# homeboard30.net
KiCad netlist of a schematic drawn in EAGLE
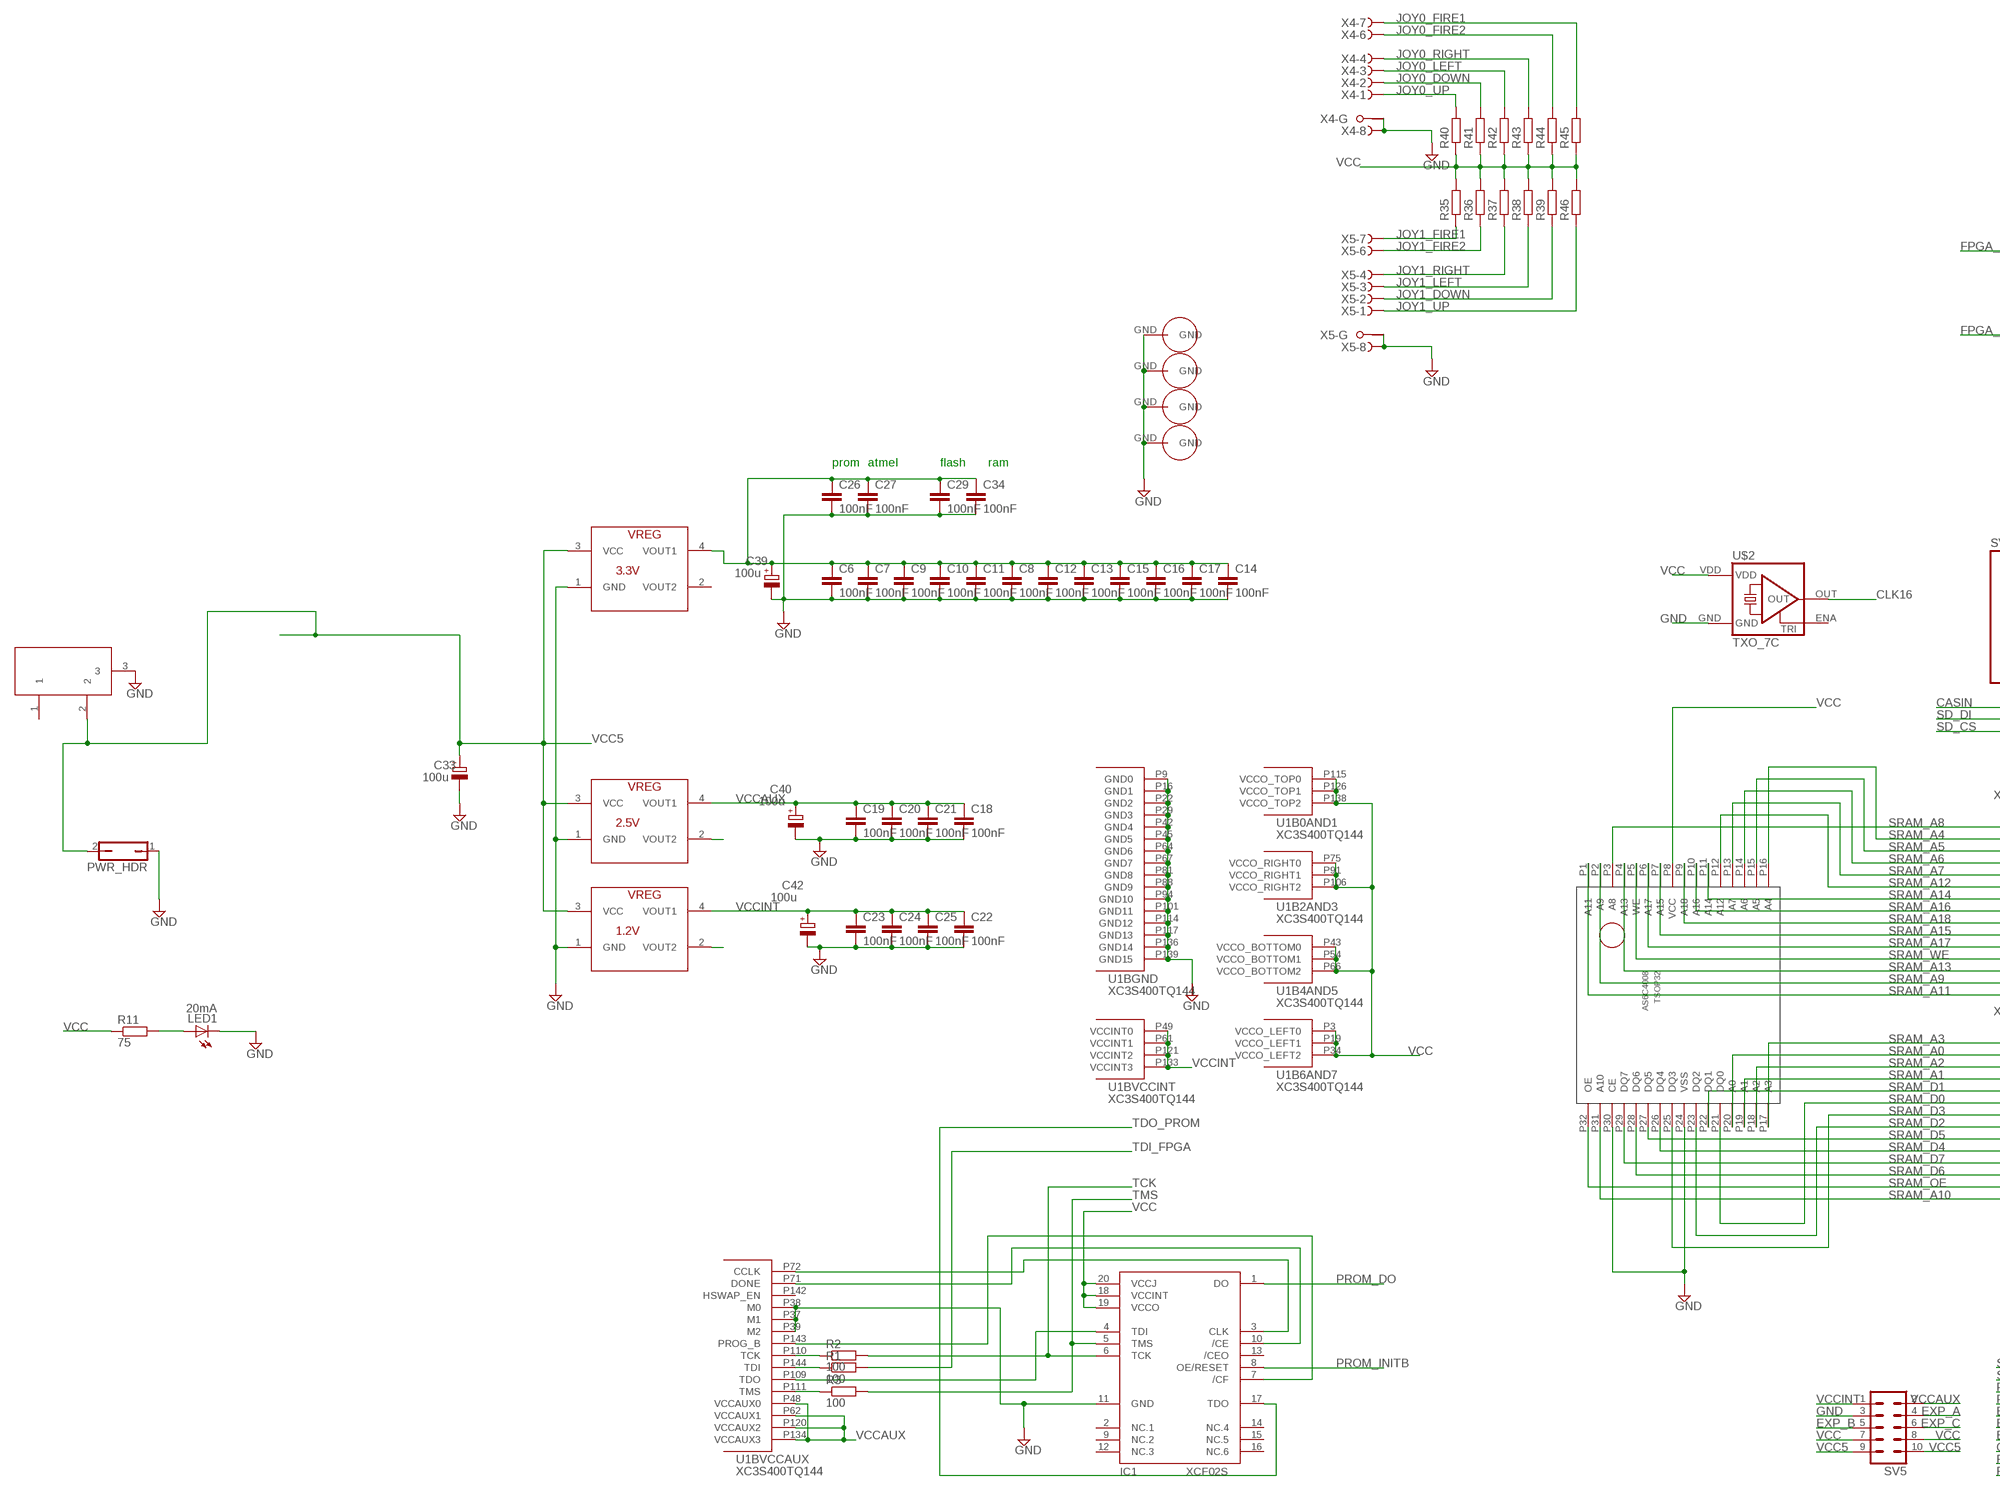
[diagram p0: schematic, sheet 1, part 1 of 3]
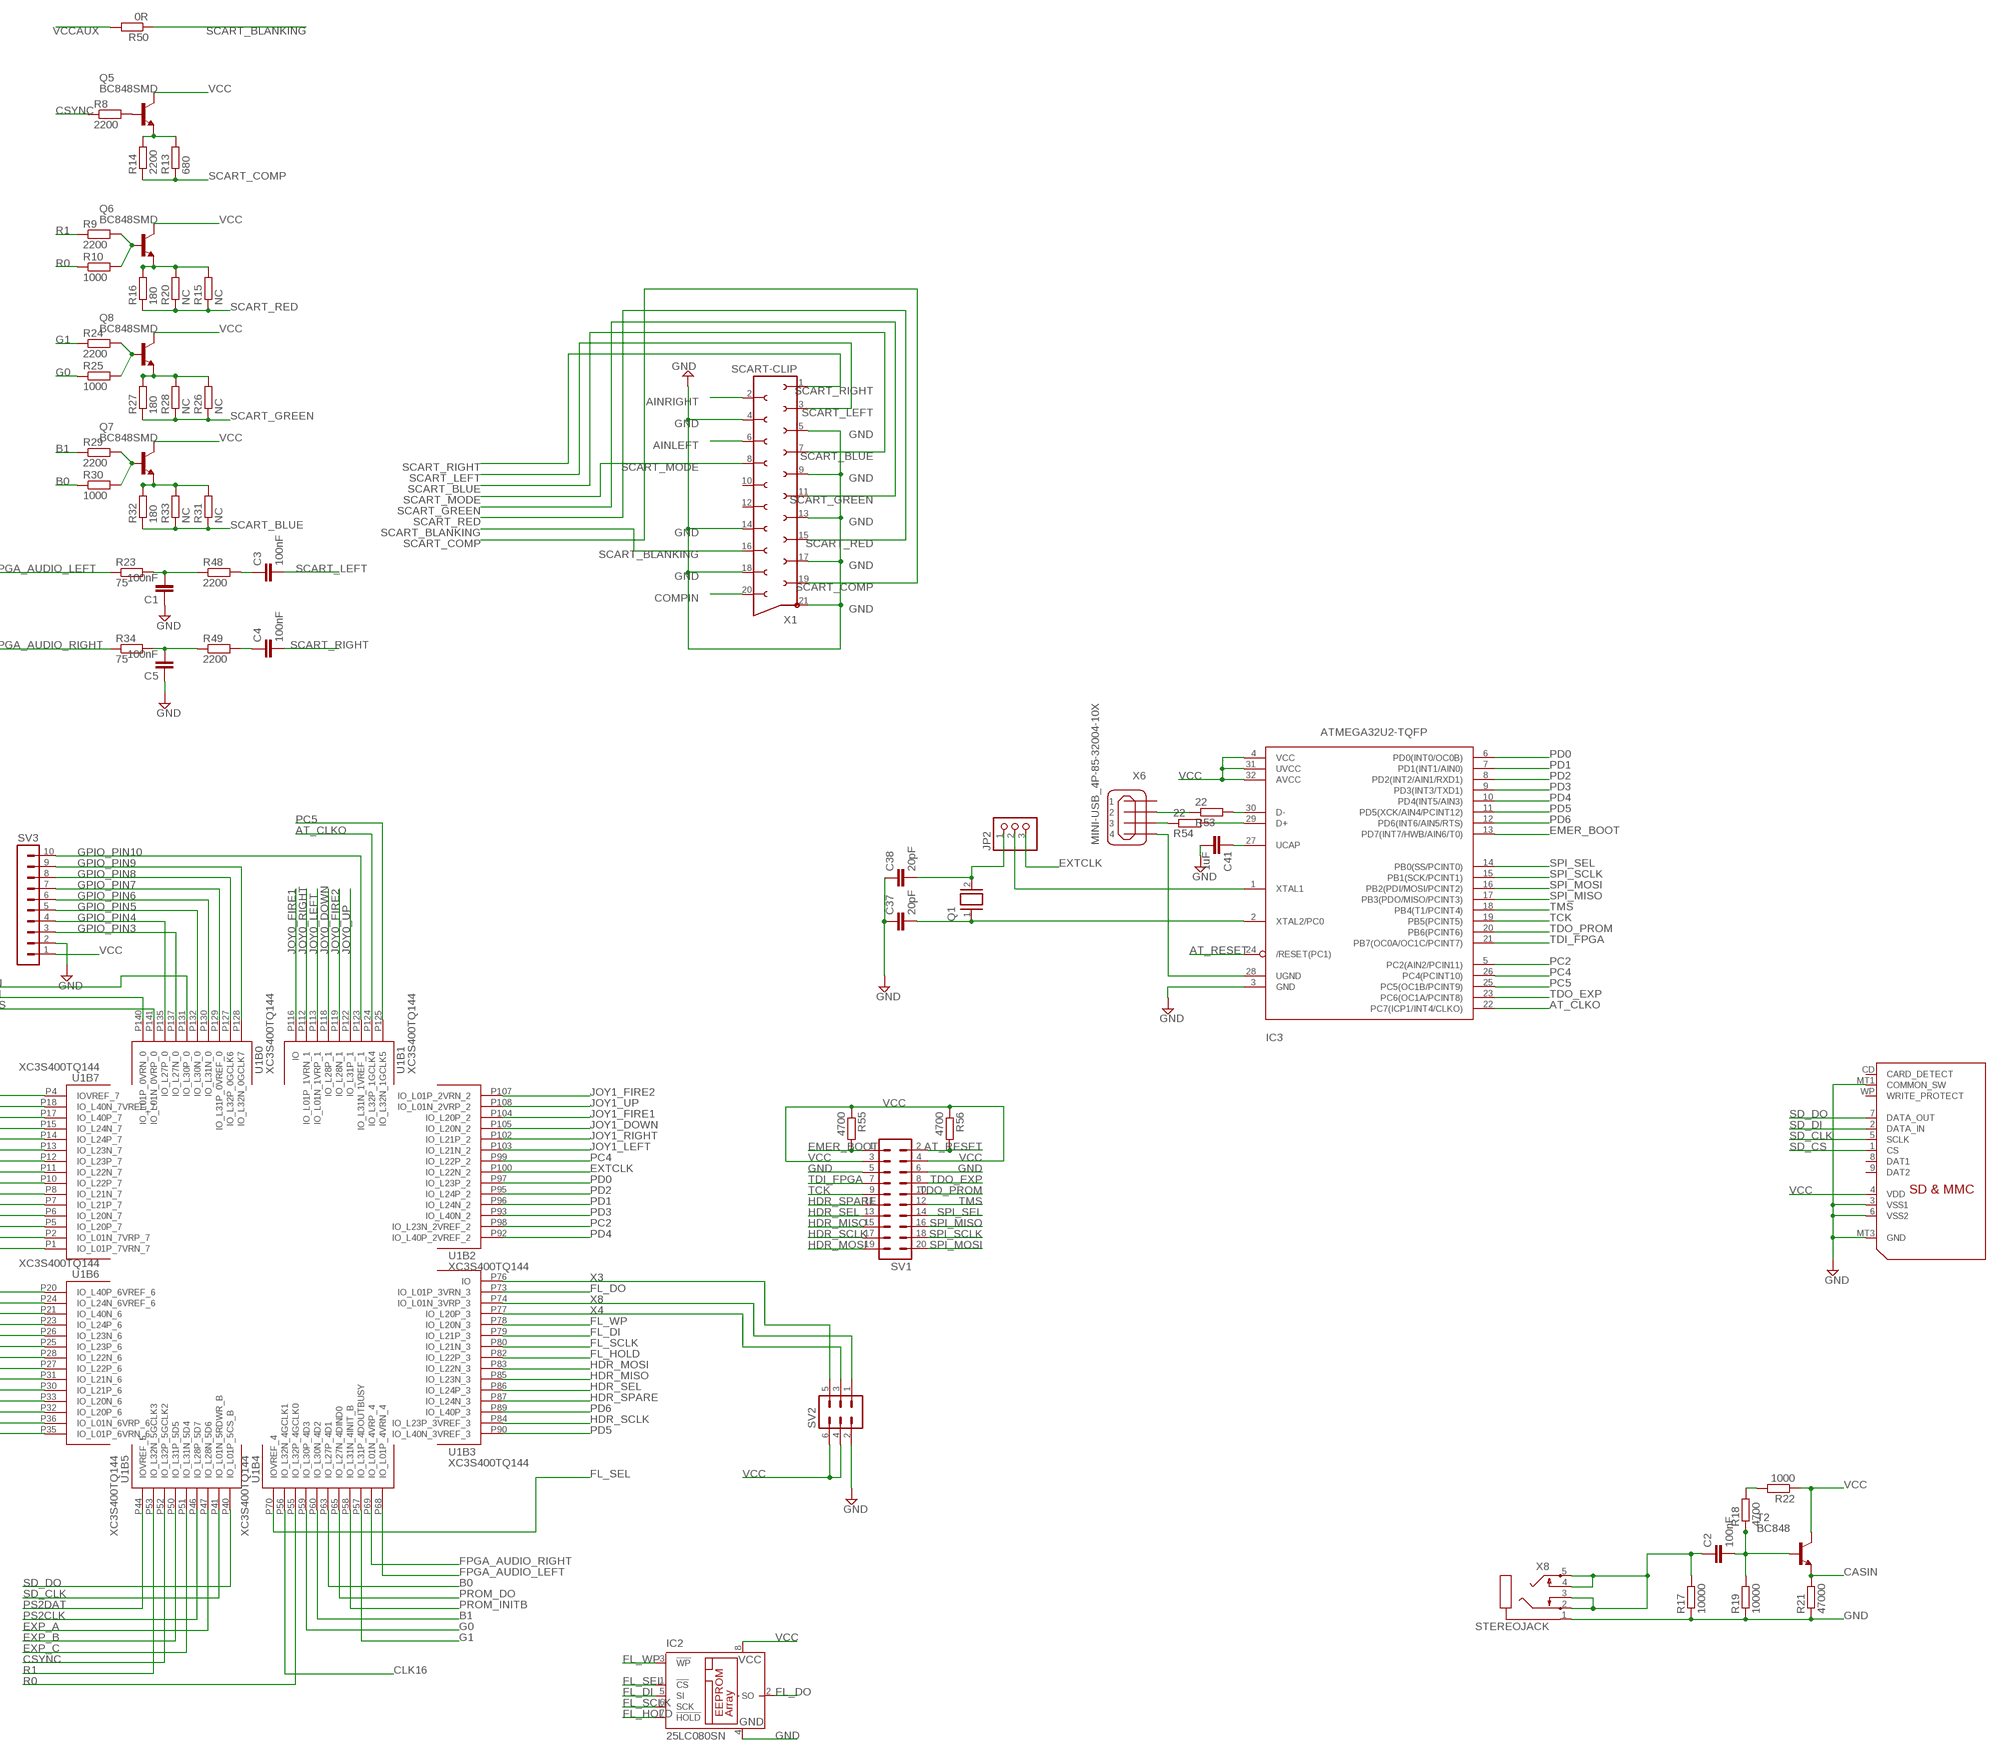
[diagram p1: schematic, sheet 1, part 2 of 3]
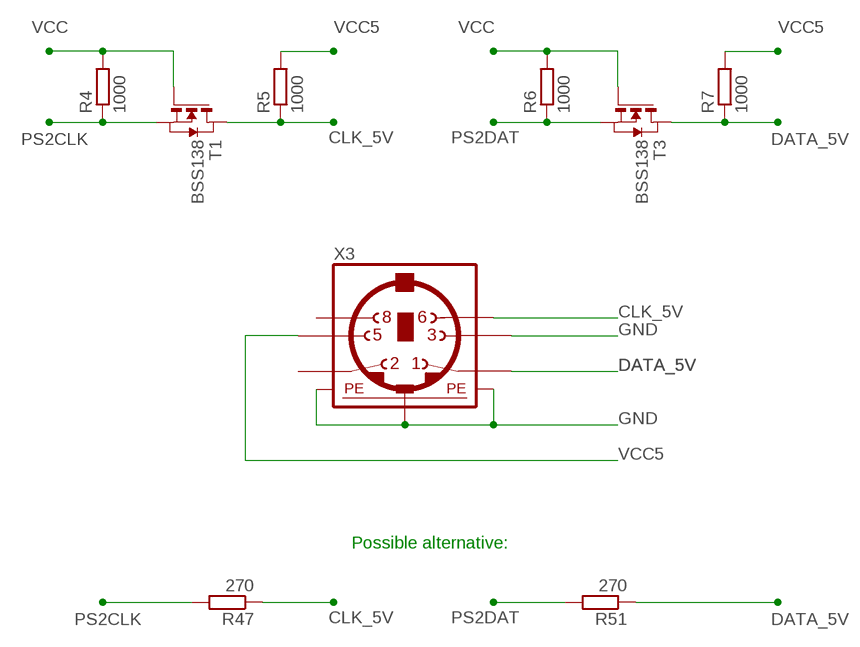
[diagram p2: schematic, sheet 1, part 3 of 3]

(export (version "E")
  (design (tool "Eeschema 10.0.6"))
  (components
    (comp (ref "C1")
      (value "100nF")
      (footprint "eagle-import:C0603")
      (libsource (lib "eagle-import") (part "resistor_C-EUC0603"))
    )
    (comp (ref "C2")
      (value "100nF")
      (footprint "eagle-import:C0603")
      (libsource (lib "eagle-import") (part "resistor_C-EUC0603"))
    )
    (comp (ref "C3")
      (value "100nF")
      (footprint "eagle-import:C0603")
      (libsource (lib "eagle-import") (part "resistor_C-EUC0603"))
    )
    (comp (ref "C4")
      (value "100nF")
      (footprint "eagle-import:C0603")
      (libsource (lib "eagle-import") (part "resistor_C-EUC0603"))
    )
    (comp (ref "C5")
      (value "100nF")
      (footprint "eagle-import:C0603")
      (libsource (lib "eagle-import") (part "resistor_C-EUC0603"))
    )
    (comp (ref "C6")
      (value "100nF")
      (footprint "eagle-import:C0603")
      (libsource (lib "eagle-import") (part "C-EUC0603"))
    )
    (comp (ref "C7")
      (value "100nF")
      (footprint "eagle-import:C0603")
      (libsource (lib "eagle-import") (part "C-EUC0603"))
    )
    (comp (ref "C8")
      (value "100nF")
      (footprint "eagle-import:C0603")
      (libsource (lib "eagle-import") (part "C-EUC0603"))
    )
    (comp (ref "C9")
      (value "100nF")
      (footprint "eagle-import:C0603")
      (libsource (lib "eagle-import") (part "C-EUC0603"))
    )
    (comp (ref "C10")
      (value "100nF")
      (footprint "eagle-import:C0603")
      (libsource (lib "eagle-import") (part "C-EUC0603"))
    )
    (comp (ref "C11")
      (value "100nF")
      (footprint "eagle-import:C0603")
      (libsource (lib "eagle-import") (part "C-EUC0603"))
    )
    (comp (ref "C12")
      (value "100nF")
      (footprint "eagle-import:C0603")
      (libsource (lib "eagle-import") (part "C-EUC0603"))
    )
    (comp (ref "C13")
      (value "100nF")
      (footprint "eagle-import:C0603")
      (libsource (lib "eagle-import") (part "C-EUC0603"))
    )
    (comp (ref "C14")
      (value "100nF")
      (footprint "eagle-import:C0603")
      (libsource (lib "eagle-import") (part "C-EUC0603"))
    )
    (comp (ref "C15")
      (value "100nF")
      (footprint "eagle-import:C0603")
      (libsource (lib "eagle-import") (part "C-EUC0603"))
    )
    (comp (ref "C16")
      (value "100nF")
      (footprint "eagle-import:C0603")
      (libsource (lib "eagle-import") (part "C-EUC0603"))
    )
    (comp (ref "C17")
      (value "100nF")
      (footprint "eagle-import:C0603")
      (libsource (lib "eagle-import") (part "C-EUC0603"))
    )
    (comp (ref "C18")
      (value "100nF")
      (footprint "eagle-import:C0603")
      (libsource (lib "eagle-import") (part "C-EUC0603"))
    )
    (comp (ref "C19")
      (value "100nF")
      (footprint "eagle-import:C0603")
      (libsource (lib "eagle-import") (part "C-EUC0603"))
    )
    (comp (ref "C20")
      (value "100nF")
      (footprint "eagle-import:C0603")
      (libsource (lib "eagle-import") (part "C-EUC0603"))
    )
    (comp (ref "C21")
      (value "100nF")
      (footprint "eagle-import:C0603")
      (libsource (lib "eagle-import") (part "C-EUC0603"))
    )
    (comp (ref "C22")
      (value "100nF")
      (footprint "eagle-import:C0603")
      (libsource (lib "eagle-import") (part "C-EUC0603"))
    )
    (comp (ref "C23")
      (value "100nF")
      (footprint "eagle-import:C0603")
      (libsource (lib "eagle-import") (part "C-EUC0603"))
    )
    (comp (ref "C24")
      (value "100nF")
      (footprint "eagle-import:C0603")
      (libsource (lib "eagle-import") (part "C-EUC0603"))
    )
    (comp (ref "C25")
      (value "100nF")
      (footprint "eagle-import:C0603")
      (libsource (lib "eagle-import") (part "C-EUC0603"))
    )
    (comp (ref "C26")
      (value "100nF")
      (footprint "eagle-import:C0603")
      (libsource (lib "eagle-import") (part "C-EUC0603"))
    )
    (comp (ref "C27")
      (value "100nF")
      (footprint "eagle-import:C0603")
      (libsource (lib "eagle-import") (part "C-EUC0603"))
    )
    (comp (ref "C29")
      (value "100nF")
      (footprint "eagle-import:C0603")
      (libsource (lib "eagle-import") (part "C-EUC0603"))
    )
    (comp (ref "C33")
      (value "100u")
      (footprint "eagle-import:PANASONIC_D")
      (libsource (lib "eagle-import") (part "CPOL-EUD"))
    )
    (comp (ref "C34")
      (value "100nF")
      (footprint "eagle-import:C0603")
      (libsource (lib "eagle-import") (part "C-EUC0603"))
    )
    (comp (ref "C37")
      (value "20pF")
      (footprint "eagle-import:C0805")
      (libsource (lib "eagle-import") (part "C-EUC0805"))
    )
    (comp (ref "C38")
      (value "20pF")
      (footprint "eagle-import:C0805")
      (libsource (lib "eagle-import") (part "C-EUC0805"))
    )
    (comp (ref "C39")
      (value "100u")
      (footprint "eagle-import:PANASONIC_D")
      (libsource (lib "eagle-import") (part "CPOL-EUD"))
    )
    (comp (ref "C40")
      (value "100u")
      (footprint "eagle-import:PANASONIC_D")
      (libsource (lib "eagle-import") (part "CPOL-EUD"))
    )
    (comp (ref "C41")
      (value "1uF")
      (footprint "eagle-import:C0805")
      (libsource (lib "eagle-import") (part "C-EUC0805"))
    )
    (comp (ref "C42")
      (value "100u")
      (footprint "eagle-import:PANASONIC_D")
      (libsource (lib "eagle-import") (part "CPOL-EUD"))
    )
    (comp (ref "IC1")
      (value "XCF02S")
      (footprint "eagle-import:VO20")
      (libsource (lib "eagle-import") (part "XCF02S"))
    )
    (comp (ref "IC2")
      (value "25LC080SN")
      (footprint "eagle-import:SO-08")
      (fields (field (name "MF") "MICROCHIP") (field (name "MPN") "25LC080/SN"))
      (libsource (lib "eagle-import") (part "25SNLC080"))
    )
    (comp (ref "IC3")
      (value "ATMEGA32U2-TQFP")
      (footprint "eagle-import:TQFP32-08")
      (libsource (lib "eagle-import") (part "ATMEGA32U2-TQFP"))
    )
    (comp (ref "JP2")
      (value "PINHD-1X3")
      (footprint "eagle-import:1X03")
      (libsource (lib "eagle-import") (part "PINHD-1X3"))
    )
    (comp (ref "LED1")
      (value "20mA")
      (footprint "eagle-import:CHIPLED_0805")
      (libsource (lib "eagle-import") (part "LEDCHIPLED_0805"))
    )
    (comp (ref "PWR_HDR")
      (value "JP1Q")
      (footprint "eagle-import:JP1")
      (libsource (lib "eagle-import") (part "JP1Q"))
    )
    (comp (ref "Q1")
      (value "XTAL/S")
      (footprint "eagle-import:QS")
      (libsource (lib "eagle-import") (part "XTAL/S"))
    )
    (comp (ref "Q5")
      (value "BC848SMD")
      (footprint "eagle-import:SOT23")
      (libsource (lib "eagle-import") (part "BC848SMD"))
    )
    (comp (ref "Q6")
      (value "BC848SMD")
      (footprint "eagle-import:SOT23")
      (libsource (lib "eagle-import") (part "BC848SMD"))
    )
    (comp (ref "Q7")
      (value "BC848SMD")
      (footprint "eagle-import:SOT23")
      (libsource (lib "eagle-import") (part "BC848SMD"))
    )
    (comp (ref "Q8")
      (value "BC848SMD")
      (footprint "eagle-import:SOT23")
      (libsource (lib "eagle-import") (part "BC848SMD"))
    )
    (comp (ref "R1")
      (value "100")
      (footprint "eagle-import:R0805")
      (libsource (lib "eagle-import") (part "R-EU_R0805"))
    )
    (comp (ref "R2")
      (value "100")
      (footprint "eagle-import:R0805")
      (libsource (lib "eagle-import") (part "R-EU_R0805"))
    )
    (comp (ref "R3")
      (value "100")
      (footprint "eagle-import:R0805")
      (libsource (lib "eagle-import") (part "R-EU_R0805"))
    )
    (comp (ref "R4")
      (value "1000")
      (footprint "eagle-import:R0805")
      (libsource (lib "eagle-import") (part "R-EU_R0805"))
    )
    (comp (ref "R5")
      (value "1000")
      (footprint "eagle-import:R0805")
      (libsource (lib "eagle-import") (part "R-EU_R0805"))
    )
    (comp (ref "R6")
      (value "1000")
      (footprint "eagle-import:R0805")
      (libsource (lib "eagle-import") (part "R-EU_R0805"))
    )
    (comp (ref "R7")
      (value "1000")
      (footprint "eagle-import:R0805")
      (libsource (lib "eagle-import") (part "R-EU_R0805"))
    )
    (comp (ref "R8")
      (value "2200")
      (footprint "eagle-import:R0805")
      (libsource (lib "eagle-import") (part "R-EU_R0805"))
    )
    (comp (ref "R9")
      (value "2200")
      (footprint "eagle-import:R0805")
      (libsource (lib "eagle-import") (part "R-EU_R0805"))
    )
    (comp (ref "R10")
      (value "1000")
      (footprint "eagle-import:R0805")
      (libsource (lib "eagle-import") (part "R-EU_R0805"))
    )
    (comp (ref "R11")
      (value "75")
      (footprint "eagle-import:M0805")
      (libsource (lib "eagle-import") (part "resistor_R-EU_M0805"))
    )
    (comp (ref "R13")
      (value "680")
      (footprint "eagle-import:R0805")
      (libsource (lib "eagle-import") (part "R-EU_R0805"))
    )
    (comp (ref "R14")
      (value "2200")
      (footprint "eagle-import:R0805")
      (libsource (lib "eagle-import") (part "R-EU_R0805"))
    )
    (comp (ref "R15")
      (value "NC")
      (footprint "eagle-import:R0805")
      (libsource (lib "eagle-import") (part "R-EU_R0805"))
    )
    (comp (ref "R16")
      (value "180")
      (footprint "eagle-import:R0805")
      (libsource (lib "eagle-import") (part "R-EU_R0805"))
    )
    (comp (ref "R17")
      (value "10000")
      (footprint "eagle-import:R0805")
      (libsource (lib "eagle-import") (part "R-EU_R0805"))
    )
    (comp (ref "R18")
      (value "4700")
      (footprint "eagle-import:R0805")
      (libsource (lib "eagle-import") (part "R-EU_R0805"))
    )
    (comp (ref "R19")
      (value "10000")
      (footprint "eagle-import:R0805")
      (libsource (lib "eagle-import") (part "R-EU_R0805"))
    )
    (comp (ref "R20")
      (value "NC")
      (footprint "eagle-import:R0805")
      (libsource (lib "eagle-import") (part "R-EU_R0805"))
    )
    (comp (ref "R21")
      (value "47000")
      (footprint "eagle-import:R0805")
      (libsource (lib "eagle-import") (part "R-EU_R0805"))
    )
    (comp (ref "R22")
      (value "1000")
      (footprint "eagle-import:R0805")
      (libsource (lib "eagle-import") (part "R-EU_R0805"))
    )
    (comp (ref "R23")
      (value "75")
      (footprint "eagle-import:M0805")
      (libsource (lib "eagle-import") (part "resistor_R-EU_M0805"))
    )
    (comp (ref "R24")
      (value "2200")
      (footprint "eagle-import:R0805")
      (libsource (lib "eagle-import") (part "R-EU_R0805"))
    )
    (comp (ref "R25")
      (value "1000")
      (footprint "eagle-import:R0805")
      (libsource (lib "eagle-import") (part "R-EU_R0805"))
    )
    (comp (ref "R26")
      (value "NC")
      (footprint "eagle-import:R0805")
      (libsource (lib "eagle-import") (part "R-EU_R0805"))
    )
    (comp (ref "R27")
      (value "180")
      (footprint "eagle-import:R0805")
      (libsource (lib "eagle-import") (part "R-EU_R0805"))
    )
    (comp (ref "R28")
      (value "NC")
      (footprint "eagle-import:R0805")
      (libsource (lib "eagle-import") (part "R-EU_R0805"))
    )
    (comp (ref "R29")
      (value "2200")
      (footprint "eagle-import:R0805")
      (libsource (lib "eagle-import") (part "R-EU_R0805"))
    )
    (comp (ref "R30")
      (value "1000")
      (footprint "eagle-import:R0805")
      (libsource (lib "eagle-import") (part "R-EU_R0805"))
    )
    (comp (ref "R31")
      (value "NC")
      (footprint "eagle-import:R0805")
      (libsource (lib "eagle-import") (part "R-EU_R0805"))
    )
    (comp (ref "R32")
      (value "180")
      (footprint "eagle-import:R0805")
      (libsource (lib "eagle-import") (part "R-EU_R0805"))
    )
    (comp (ref "R33")
      (value "NC")
      (footprint "eagle-import:R0805")
      (libsource (lib "eagle-import") (part "R-EU_R0805"))
    )
    (comp (ref "R34")
      (value "75")
      (footprint "eagle-import:M0805")
      (libsource (lib "eagle-import") (part "resistor_R-EU_M0805"))
    )
    (comp (ref "R35")
      (value "R-EU_M0805")
      (footprint "eagle-import:M0805")
      (libsource (lib "eagle-import") (part "resistor_R-EU_M0805"))
    )
    (comp (ref "R36")
      (value "R-EU_M0805")
      (footprint "eagle-import:M0805")
      (libsource (lib "eagle-import") (part "resistor_R-EU_M0805"))
    )
    (comp (ref "R37")
      (value "R-EU_M0805")
      (footprint "eagle-import:M0805")
      (libsource (lib "eagle-import") (part "resistor_R-EU_M0805"))
    )
    (comp (ref "R38")
      (value "R-EU_M0805")
      (footprint "eagle-import:M0805")
      (libsource (lib "eagle-import") (part "resistor_R-EU_M0805"))
    )
    (comp (ref "R39")
      (value "R-EU_M0805")
      (footprint "eagle-import:M0805")
      (libsource (lib "eagle-import") (part "resistor_R-EU_M0805"))
    )
    (comp (ref "R40")
      (value "R-EU_M0805")
      (footprint "eagle-import:M0805")
      (libsource (lib "eagle-import") (part "resistor_R-EU_M0805"))
    )
    (comp (ref "R41")
      (value "R-EU_M0805")
      (footprint "eagle-import:M0805")
      (libsource (lib "eagle-import") (part "resistor_R-EU_M0805"))
    )
    (comp (ref "R42")
      (value "R-EU_M0805")
      (footprint "eagle-import:M0805")
      (libsource (lib "eagle-import") (part "resistor_R-EU_M0805"))
    )
    (comp (ref "R43")
      (value "R-EU_M0805")
      (footprint "eagle-import:M0805")
      (libsource (lib "eagle-import") (part "resistor_R-EU_M0805"))
    )
    (comp (ref "R44")
      (value "R-EU_M0805")
      (footprint "eagle-import:M0805")
      (libsource (lib "eagle-import") (part "resistor_R-EU_M0805"))
    )
    (comp (ref "R45")
      (value "R-EU_M0805")
      (footprint "eagle-import:M0805")
      (libsource (lib "eagle-import") (part "resistor_R-EU_M0805"))
    )
    (comp (ref "R46")
      (value "R-EU_M0805")
      (footprint "eagle-import:M0805")
      (libsource (lib "eagle-import") (part "resistor_R-EU_M0805"))
    )
    (comp (ref "R47")
      (value "270")
      (footprint "eagle-import:R0805")
      (libsource (lib "eagle-import") (part "R-EU_R0805"))
    )
    (comp (ref "R48")
      (value "2200")
      (footprint "eagle-import:M0805")
      (libsource (lib "eagle-import") (part "resistor_R-EU_M0805"))
    )
    (comp (ref "R49")
      (value "2200")
      (footprint "eagle-import:M0805")
      (libsource (lib "eagle-import") (part "resistor_R-EU_M0805"))
    )
    (comp (ref "R50")
      (value "0R")
      (footprint "eagle-import:M0805")
      (libsource (lib "eagle-import") (part "resistor_R-EU_M0805"))
    )
    (comp (ref "R51")
      (value "270")
      (footprint "eagle-import:R0805")
      (libsource (lib "eagle-import") (part "R-EU_R0805"))
    )
    (comp (ref "R53")
      (value "22")
      (footprint "eagle-import:R0805")
      (libsource (lib "eagle-import") (part "R-EU_R0805"))
    )
    (comp (ref "R54")
      (value "22")
      (footprint "eagle-import:R0805")
      (libsource (lib "eagle-import") (part "R-EU_R0805"))
    )
    (comp (ref "R55")
      (value "4700")
      (footprint "eagle-import:R0805")
      (libsource (lib "eagle-import") (part "R-EU_R0805"))
    )
    (comp (ref "R56")
      (value "4700")
      (footprint "eagle-import:R0805")
      (libsource (lib "eagle-import") (part "R-EU_R0805"))
    )
    (comp (ref "REG1.2")
      (value "1.2V")
      (footprint "eagle-import:SOT223")
      (libsource (lib "eagle-import") (part "NX1117"))
    )
    (comp (ref "REG2.5")
      (value "2.5V")
      (footprint "eagle-import:SOT223")
      (libsource (lib "eagle-import") (part "NX1117"))
    )
    (comp (ref "REG3.3")
      (value "3.3V")
      (footprint "eagle-import:SOT223")
      (libsource (lib "eagle-import") (part "NX1117"))
    )
    (comp (ref "SV1")
      (value "MA10-2")
      (footprint "eagle-import:MA10-2")
      (fields (field (name "OC_FARNELL") "unknown") (field (name "OC_NEWARK") "unknown"))
      (libsource (lib "eagle-import") (part "MA10-2"))
    )
    (comp (ref "SV2")
      (value "MA03-2")
      (footprint "eagle-import:MA03-2")
      (libsource (lib "eagle-import") (part "MA03-2"))
    )
    (comp (ref "SV3")
      (value "MA10-1")
      (footprint "eagle-import:MA10-1")
      (libsource (lib "eagle-import") (part "MA10-1"))
    )
    (comp (ref "SV5")
      (value "MA05-2")
      (footprint "eagle-import:MA05-2")
      (libsource (lib "eagle-import") (part "MA05-2"))
    )
    (comp (ref "T1")
      (value "BSS138")
      (footprint "eagle-import:SOT-23")
      (libsource (lib "eagle-import") (part "NMOSSOT23"))
    )
    (comp (ref "T2")
      (value "BC848")
      (footprint "eagle-import:SOT23")
      (libsource (lib "eagle-import") (part "BC848"))
    )
    (comp (ref "T3")
      (value "BSS138")
      (footprint "eagle-import:SOT-23")
      (libsource (lib "eagle-import") (part "NMOSSOT23"))
    )
    (comp (ref "U$1")
      (value "GNDHOLE")
      (footprint "eagle-import:GNDHOLE")
      (libsource (lib "eagle-import") (part "GNDHOLE"))
    )
    (comp (ref "U$2")
      (value "TXO_7C")
      (footprint "eagle-import:OSC_7C")
      (libsource (lib "eagle-import") (part "TXO_7C"))
    )
    (comp (ref "U$3")
      (value "SDMMCNOHOLE")
      (footprint "eagle-import:SDCARD-NOHOLE")
      (libsource (lib "eagle-import") (part "SDMMCNOHOLE"))
    )
    (comp (ref "U$6")
      (value "AS6C4008")
      (footprint "eagle-import:TSOP32")
      (libsource (lib "eagle-import") (part "AS6C4008"))
    )
    (comp (ref "U$7")
      (value "GNDHOLE")
      (footprint "eagle-import:GNDHOLE")
      (libsource (lib "eagle-import") (part "GNDHOLE"))
    )
    (comp (ref "U$8")
      (value "GNDHOLE")
      (footprint "eagle-import:GNDHOLE")
      (libsource (lib "eagle-import") (part "GNDHOLE"))
    )
    (comp (ref "U$9")
      (value "GNDHOLE")
      (footprint "eagle-import:GNDHOLE")
      (libsource (lib "eagle-import") (part "GNDHOLE"))
    )
    (comp (ref "U1")
      (value "XC3S400TQ144")
      (footprint "eagle-import:TQ144")
      (libsource (lib "eagle-import") (part "XC3S400TQ144"))
    )
    (comp (ref "X1")
      (value "SCART-CLIP")
      (footprint "eagle-import:SCART-CLIP")
      (libsource (lib "eagle-import") (part "SCART-CLIP"))
    )
    (comp (ref "X3")
      (value "MINI_DIN_6")
      (footprint "eagle-import:M_DIN6")
      (libsource (lib "eagle-import") (part "MINI_DIN_6"))
    )
    (comp (ref "X4")
      (value "F09HPS")
      (footprint "eagle-import:F09HP")
      (libsource (lib "eagle-import") (part "F09HPS"))
    )
    (comp (ref "X5")
      (value "F09HPS")
      (footprint "eagle-import:F09HP")
      (libsource (lib "eagle-import") (part "F09HPS"))
    )
    (comp (ref "X6")
      (value "MINI-USB_4P-85-32004-10X")
      (footprint "eagle-import:85-32004-10X")
      (libsource (lib "eagle-import") (part "MINI-USB_4P-85-32004-10X"))
    )
    (comp (ref "X7")
      (value "DC21MMX")
      (footprint "eagle-import:DC-21MM")
      (libsource (lib "eagle-import") (part "DC21MMX"))
    )
    (comp (ref "X8")
      (value "STEREOJACK")
      (footprint "eagle-import:20-0137")
      (libsource (lib "eagle-import") (part "STEREOJACK"))
    )
  )
  (nets
    (net (code "1") (name "/1") (class "Default")
      (node (ref "X7") (pin "1") (pinfunction "1_1") (pintype "power_in"))
    )
    (net (code "2") (name "/AINLEFT") (class "Default")
      (node (ref "X1") (pin "6") (pinfunction "6_6") (pintype "passive"))
    )
    (net (code "3") (name "/AINRIGHT") (class "Default")
      (node (ref "X1") (pin "2") (pinfunction "2_2") (pintype "passive"))
    )
    (net (code "4") (name "/AT_CLKO") (class "Default")
      (node (ref "IC3") (pin "22") (pinfunction "PC7(ICP1/INT4/CLKO)_22") (pintype "bidirectional"))
      (node (ref "U1") (pin "P124") (pinfunction "IO_L32P_1GCLK4_P124") (pintype "bidirectional"))
    )
    (net (code "5") (name "/AT_RESET") (class "Default")
      (node (ref "IC3") (pin "24") (pinfunction "/RESET(PC1)_24") (pintype "bidirectional"))
      (node (ref "R56") (pin "2") (pinfunction "2_2") (pintype "passive"))
      (node (ref "SV1") (pin "2") (pinfunction "2_2") (pintype "passive"))
    )
    (net (code "6") (name "/B0") (class "Default")
      (node (ref "R30") (pin "1") (pinfunction "1_1") (pintype "passive"))
      (node (ref "U1") (pin "P63") (pinfunction "IO_L27P_4D1_P63") (pintype "bidirectional"))
    )
    (net (code "7") (name "/B1") (class "Default")
      (node (ref "R29") (pin "1") (pinfunction "1_1") (pintype "passive"))
      (node (ref "U1") (pin "P60") (pinfunction "IO_L30N_4D2_P60") (pintype "bidirectional"))
    )
    (net (code "8") (name "/CASIN") (class "Default")
      (node (ref "R21") (pin "2") (pinfunction "2_2") (pintype "passive"))
      (node (ref "T2") (pin "2") (pinfunction "E_2") (pintype "passive"))
      (node (ref "U1") (pin "P131") (pinfunction "IO_L30P_0_P131") (pintype "bidirectional"))
    )
    (net (code "9") (name "/CLK16") (class "Default")
      (node (ref "U$2") (pin "OUT") (pinfunction "OUT_OUT") (pintype "output"))
      (node (ref "U1") (pin "P56") (pinfunction "IO_L32N_4GCLK1_P56") (pintype "bidirectional"))
    )
    (net (code "10") (name "/CLK_5V") (class "Default")
      (node (ref "R47") (pin "1") (pinfunction "1_1") (pintype "passive"))
      (node (ref "R5") (pin "1") (pinfunction "1_1") (pintype "passive"))
      (node (ref "T1") (pin "1") (pinfunction "D_1") (pintype "passive"))
      (node (ref "X3") (pin "6") (pinfunction "6_6") (pintype "passive"))
    )
    (net (code "11") (name "/COMPIN") (class "Default")
      (node (ref "X1") (pin "20") (pinfunction "20_20") (pintype "passive"))
    )
    (net (code "12") (name "/CSYNC") (class "Default")
      (node (ref "R8") (pin "1") (pinfunction "1_1") (pintype "passive"))
      (node (ref "U1") (pin "P52") (pinfunction "IO_L32P_5GCLK2_P52") (pintype "bidirectional"))
    )
    (net (code "13") (name "/DATA_5V") (class "Default")
      (node (ref "R51") (pin "1") (pinfunction "1_1") (pintype "passive"))
      (node (ref "R7") (pin "1") (pinfunction "1_1") (pintype "passive"))
      (node (ref "T3") (pin "1") (pinfunction "D_1") (pintype "passive"))
      (node (ref "X3") (pin "1") (pinfunction "1_1") (pintype "passive"))
    )
    (net (code "14") (name "/EMER_BOOT") (class "Default")
      (node (ref "IC3") (pin "13") (pinfunction "PD7(INT7/HWB/AIN6/T0)_13") (pintype "bidirectional"))
      (node (ref "R55") (pin "2") (pinfunction "2_2") (pintype "passive"))
      (node (ref "SV1") (pin "1") (pinfunction "1_1") (pintype "passive"))
    )
    (net (code "15") (name "/EXP_A") (class "Default")
      (node (ref "SV5") (pin "4") (pinfunction "4_4") (pintype "passive"))
      (node (ref "U1") (pin "P47") (pinfunction "IO_L28N_5D6_P47") (pintype "bidirectional"))
    )
    (net (code "16") (name "/EXP_B") (class "Default")
      (node (ref "SV5") (pin "5") (pinfunction "5_5") (pintype "passive"))
      (node (ref "U1") (pin "P50") (pinfunction "IO_L31P_5D5_P50") (pintype "bidirectional"))
    )
    (net (code "17") (name "/EXP_C") (class "Default")
      (node (ref "SV5") (pin "6") (pinfunction "6_6") (pintype "passive"))
      (node (ref "U1") (pin "P51") (pinfunction "IO_L31N_5D4_P51") (pintype "bidirectional"))
    )
    (net (code "18") (name "/EXTCLK") (class "Default")
      (node (ref "JP2") (pin "3") (pinfunction "3_3") (pintype "passive"))
      (node (ref "U1") (pin "P100") (pinfunction "IO_L22N_2_P100") (pintype "bidirectional"))
    )
    (net (code "19") (name "/FL_DI") (class "Default")
      (node (ref "IC2") (pin "5") (pinfunction "SI_5") (pintype "input"))
      (node (ref "U1") (pin "P79") (pinfunction "IO_L21P_3_P79") (pintype "bidirectional"))
    )
    (net (code "20") (name "/FL_DO") (class "Default")
      (node (ref "IC2") (pin "2") (pinfunction "SO_2") (pintype "bidirectional"))
      (node (ref "U1") (pin "P73") (pinfunction "IO_L01P_3VRN_3_P73") (pintype "bidirectional"))
    )
    (net (code "21") (name "/FL_HOLD") (class "Default")
      (node (ref "IC2") (pin "7") (pinfunction "~{HOLD}_7") (pintype "input"))
      (node (ref "U1") (pin "P82") (pinfunction "IO_L22P_3_P82") (pintype "bidirectional"))
    )
    (net (code "22") (name "/FL_SCLK") (class "Default")
      (node (ref "IC2") (pin "6") (pinfunction "SCK_6") (pintype "input"))
      (node (ref "U1") (pin "P80") (pinfunction "IO_L21N_3_P80") (pintype "bidirectional"))
    )
    (net (code "23") (name "/FL_SEL") (class "Default")
      (node (ref "IC2") (pin "1") (pinfunction "~{CS}_1") (pintype "input"))
      (node (ref "U1") (pin "P70") (pinfunction "IOVREF_4_P70") (pintype "bidirectional"))
    )
    (net (code "24") (name "/FL_WP") (class "Default")
      (node (ref "IC2") (pin "3") (pinfunction "~{WP}_3") (pintype "input"))
      (node (ref "U1") (pin "P78") (pinfunction "IO_L20N_3_P78") (pintype "bidirectional"))
    )
    (net (code "25") (name "/FPGA_AUDIO_LEFT") (class "Default")
      (node (ref "R23") (pin "1") (pinfunction "1_1") (pintype "passive"))
      (node (ref "U1") (pin "P68") (pinfunction "IO_L01P_4VRN_4_P68") (pintype "bidirectional"))
    )
    (net (code "26") (name "/FPGA_AUDIO_RIGHT") (class "Default")
      (node (ref "R34") (pin "1") (pinfunction "1_1") (pintype "passive"))
      (node (ref "U1") (pin "P69") (pinfunction "IO_L01N_4VRP_4_P69") (pintype "bidirectional"))
    )
    (net (code "27") (name "/G0") (class "Default")
      (node (ref "R25") (pin "1") (pinfunction "1_1") (pintype "passive"))
      (node (ref "U1") (pin "P59") (pinfunction "IO_L30P_4D3_P59") (pintype "bidirectional"))
    )
    (net (code "28") (name "/G1") (class "Default")
      (node (ref "R24") (pin "1") (pinfunction "1_1") (pintype "passive"))
      (node (ref "U1") (pin "P57") (pinfunction "IO_L31P_4DOUTBUSY_P57") (pintype "bidirectional"))
    )
    (net (code "29") (name "/GPIO_PIN3") (class "Default")
      (node (ref "SV3") (pin "3") (pinfunction "3_3") (pintype "passive"))
      (node (ref "U1") (pin "P137") (pinfunction "IO_L27N_0_P137") (pintype "bidirectional"))
    )
    (net (code "30") (name "/GPIO_PIN4") (class "Default")
      (node (ref "SV3") (pin "4") (pinfunction "4_4") (pintype "passive"))
      (node (ref "U1") (pin "P135") (pinfunction "IO_L27P_0_P135") (pintype "bidirectional"))
    )
    (net (code "31") (name "/GPIO_PIN5") (class "Default")
      (node (ref "SV3") (pin "5") (pinfunction "5_5") (pintype "passive"))
      (node (ref "U1") (pin "P132") (pinfunction "IO_L30N_0_P132") (pintype "bidirectional"))
    )
    (net (code "32") (name "/GPIO_PIN6") (class "Default")
      (node (ref "SV3") (pin "6") (pinfunction "6_6") (pintype "passive"))
      (node (ref "U1") (pin "P130") (pinfunction "IO_L31N_0_P130") (pintype "bidirectional"))
    )
    (net (code "33") (name "/GPIO_PIN7") (class "Default")
      (node (ref "SV3") (pin "7") (pinfunction "7_7") (pintype "passive"))
      (node (ref "U1") (pin "P129") (pinfunction "IO_L31P_0VREF_0_P129") (pintype "bidirectional"))
    )
    (net (code "34") (name "/GPIO_PIN8") (class "Default")
      (node (ref "SV3") (pin "8") (pinfunction "8_8") (pintype "passive"))
      (node (ref "U1") (pin "P127") (pinfunction "IO_L32P_0GCLK6_P127") (pintype "bidirectional"))
    )
    (net (code "35") (name "/GPIO_PIN9") (class "Default")
      (node (ref "SV3") (pin "9") (pinfunction "9_9") (pintype "passive"))
      (node (ref "U1") (pin "P128") (pinfunction "IO_L32N_0GCLK7_P128") (pintype "bidirectional"))
    )
    (net (code "36") (name "/GPIO_PIN10") (class "Default")
      (node (ref "SV3") (pin "10") (pinfunction "10_10") (pintype "passive"))
      (node (ref "U1") (pin "P123") (pinfunction "IO_L31N_1VREF_1_P123") (pintype "bidirectional"))
    )
    (net (code "37") (name "/HDR_MISO") (class "Default")
      (node (ref "SV1") (pin "15") (pinfunction "15_15") (pintype "passive"))
      (node (ref "U1") (pin "P85") (pinfunction "IO_L23N_3_P85") (pintype "bidirectional"))
    )
    (net (code "38") (name "/HDR_MOSI") (class "Default")
      (node (ref "SV1") (pin "19") (pinfunction "19_19") (pintype "passive"))
      (node (ref "U1") (pin "P83") (pinfunction "IO_L22N_3_P83") (pintype "bidirectional"))
    )
    (net (code "39") (name "/HDR_SCLK") (class "Default")
      (node (ref "SV1") (pin "17") (pinfunction "17_17") (pintype "passive"))
      (node (ref "U1") (pin "P84") (pinfunction "IO_L23P_3VREF_3_P84") (pintype "bidirectional"))
    )
    (net (code "40") (name "/HDR_SEL") (class "Default")
      (node (ref "SV1") (pin "13") (pinfunction "13_13") (pintype "passive"))
      (node (ref "U1") (pin "P86") (pinfunction "IO_L24P_3_P86") (pintype "bidirectional"))
    )
    (net (code "41") (name "/HDR_SPARE") (class "Default")
      (node (ref "SV1") (pin "11") (pinfunction "11_11") (pintype "passive"))
      (node (ref "U1") (pin "P87") (pinfunction "IO_L24N_3_P87") (pintype "bidirectional"))
    )
    (net (code "42") (name "/JOY0_DOWN") (class "Default")
      (node (ref "R41") (pin "2") (pinfunction "2_2") (pintype "passive"))
      (node (ref "U1") (pin "P118") (pinfunction "IO_L28P_1_P118") (pintype "bidirectional"))
      (node (ref "X4") (pin "2") (pinfunction "F_2") (pintype "passive"))
    )
    (net (code "43") (name "/JOY0_FIRE1") (class "Default")
      (node (ref "R45") (pin "2") (pinfunction "2_2") (pintype "passive"))
      (node (ref "U1") (pin "P116") (pinfunction "IO_P116") (pintype "bidirectional"))
      (node (ref "X4") (pin "7") (pinfunction "F_7") (pintype "passive"))
    )
    (net (code "44") (name "/JOY0_FIRE2") (class "Default")
      (node (ref "R44") (pin "2") (pinfunction "2_2") (pintype "passive"))
      (node (ref "U1") (pin "P119") (pinfunction "IO_L28N_1_P119") (pintype "bidirectional"))
      (node (ref "X4") (pin "6") (pinfunction "F_6") (pintype "passive"))
    )
    (net (code "45") (name "/JOY0_LEFT") (class "Default")
      (node (ref "R42") (pin "2") (pinfunction "2_2") (pintype "passive"))
      (node (ref "U1") (pin "P113") (pinfunction "IO_L01N_1VRP_1_P113") (pintype "bidirectional"))
      (node (ref "X4") (pin "3") (pinfunction "F_3") (pintype "passive"))
    )
    (net (code "46") (name "/JOY0_RIGHT") (class "Default")
      (node (ref "R43") (pin "2") (pinfunction "2_2") (pintype "passive"))
      (node (ref "U1") (pin "P112") (pinfunction "IO_L01P_1VRN_1_P112") (pintype "bidirectional"))
      (node (ref "X4") (pin "4") (pinfunction "F_4") (pintype "passive"))
    )
    (net (code "47") (name "/JOY0_UP") (class "Default")
      (node (ref "R40") (pin "2") (pinfunction "2_2") (pintype "passive"))
      (node (ref "U1") (pin "P122") (pinfunction "IO_L31P_1_P122") (pintype "bidirectional"))
      (node (ref "X4") (pin "1") (pinfunction "F_1") (pintype "passive"))
    )
    (net (code "48") (name "/JOY1_DOWN") (class "Default")
      (node (ref "R39") (pin "1") (pinfunction "1_1") (pintype "passive"))
      (node (ref "U1") (pin "P105") (pinfunction "IO_L20N_2_P105") (pintype "bidirectional"))
      (node (ref "X5") (pin "2") (pinfunction "F_2") (pintype "passive"))
    )
    (net (code "49") (name "/JOY1_FIRE1") (class "Default")
      (node (ref "R35") (pin "1") (pinfunction "1_1") (pintype "passive"))
      (node (ref "U1") (pin "P104") (pinfunction "IO_L20P_2_P104") (pintype "bidirectional"))
      (node (ref "X5") (pin "7") (pinfunction "F_7") (pintype "passive"))
    )
    (net (code "50") (name "/JOY1_FIRE2") (class "Default")
      (node (ref "R36") (pin "1") (pinfunction "1_1") (pintype "passive"))
      (node (ref "U1") (pin "P107") (pinfunction "IO_L01P_2VRN_2_P107") (pintype "bidirectional"))
      (node (ref "X5") (pin "6") (pinfunction "F_6") (pintype "passive"))
    )
    (net (code "51") (name "/JOY1_LEFT") (class "Default")
      (node (ref "R38") (pin "1") (pinfunction "1_1") (pintype "passive"))
      (node (ref "U1") (pin "P103") (pinfunction "IO_L21N_2_P103") (pintype "bidirectional"))
      (node (ref "X5") (pin "3") (pinfunction "F_3") (pintype "passive"))
    )
    (net (code "52") (name "/JOY1_RIGHT") (class "Default")
      (node (ref "R37") (pin "1") (pinfunction "1_1") (pintype "passive"))
      (node (ref "U1") (pin "P102") (pinfunction "IO_L21P_2_P102") (pintype "bidirectional"))
      (node (ref "X5") (pin "4") (pinfunction "F_4") (pintype "passive"))
    )
    (net (code "53") (name "/JOY1_UP") (class "Default")
      (node (ref "R46") (pin "1") (pinfunction "1_1") (pintype "passive"))
      (node (ref "U1") (pin "P108") (pinfunction "IO_L01N_2VRP_2_P108") (pintype "bidirectional"))
      (node (ref "X5") (pin "1") (pinfunction "F_1") (pintype "passive"))
    )
    (net (code "54") (name "/PC2") (class "Default")
      (node (ref "IC3") (pin "5") (pinfunction "PC2(AIN2/PCIN11)_5") (pintype "bidirectional"))
      (node (ref "U1") (pin "P98") (pinfunction "IO_L23N_2VREF_2_P98") (pintype "bidirectional"))
    )
    (net (code "55") (name "/PC4") (class "Default")
      (node (ref "IC3") (pin "26") (pinfunction "PC4(PCINT10)_26") (pintype "bidirectional"))
      (node (ref "U1") (pin "P99") (pinfunction "IO_L22P_2_P99") (pintype "bidirectional"))
    )
    (net (code "56") (name "/PC5") (class "Default")
      (node (ref "IC3") (pin "25") (pinfunction "PC5(OC1B/PCINT9)_25") (pintype "bidirectional"))
      (node (ref "U1") (pin "P125") (pinfunction "IO_L32N_1GCLK5_P125") (pintype "bidirectional"))
    )
    (net (code "57") (name "/PD0") (class "Default")
      (node (ref "IC3") (pin "6") (pinfunction "PD0(INT0/OC0B)_6") (pintype "bidirectional"))
      (node (ref "U1") (pin "P97") (pinfunction "IO_L23P_2_P97") (pintype "bidirectional"))
    )
    (net (code "58") (name "/PD1") (class "Default")
      (node (ref "IC3") (pin "7") (pinfunction "PD1(INT1/AIN0)_7") (pintype "bidirectional"))
      (node (ref "U1") (pin "P96") (pinfunction "IO_L24N_2_P96") (pintype "bidirectional"))
    )
    (net (code "59") (name "/PD2") (class "Default")
      (node (ref "IC3") (pin "8") (pinfunction "PD2(INT2/AIN1/RXD1)_8") (pintype "bidirectional"))
      (node (ref "U1") (pin "P95") (pinfunction "IO_L24P_2_P95") (pintype "bidirectional"))
    )
    (net (code "60") (name "/PD3") (class "Default")
      (node (ref "IC3") (pin "9") (pinfunction "PD3(INT3/TXD1)_9") (pintype "bidirectional"))
      (node (ref "U1") (pin "P93") (pinfunction "IO_L40N_2_P93") (pintype "bidirectional"))
    )
    (net (code "61") (name "/PD4") (class "Default")
      (node (ref "IC3") (pin "10") (pinfunction "PD4(INT5/AIN3)_10") (pintype "bidirectional"))
      (node (ref "U1") (pin "P92") (pinfunction "IO_L40P_2VREF_2_P92") (pintype "bidirectional"))
    )
    (net (code "62") (name "/PD5") (class "Default")
      (node (ref "IC3") (pin "11") (pinfunction "PD5(XCK/AIN4/PCINT12)_11") (pintype "bidirectional"))
      (node (ref "U1") (pin "P90") (pinfunction "IO_L40N_3VREF_3_P90") (pintype "bidirectional"))
    )
    (net (code "63") (name "/PD6") (class "Default")
      (node (ref "IC3") (pin "12") (pinfunction "PD6(INT6/AIN5/RTS)_12") (pintype "bidirectional"))
      (node (ref "U1") (pin "P89") (pinfunction "IO_L40P_3_P89") (pintype "bidirectional"))
    )
    (net (code "64") (name "/PROM_DO") (class "Default")
      (node (ref "IC1") (pin "1") (pinfunction "DO_1") (pintype "bidirectional"))
      (node (ref "U1") (pin "P65") (pinfunction "IO_L27N_4DIND0_P65") (pintype "bidirectional"))
    )
    (net (code "65") (name "/PROM_INITB") (class "Default")
      (node (ref "IC1") (pin "8") (pinfunction "OE/RESET_8") (pintype "bidirectional"))
      (node (ref "U1") (pin "P58") (pinfunction "IO_L31N_4INIT_B_P58") (pintype "bidirectional"))
    )
    (net (code "66") (name "/PS2CLK") (class "Default")
      (node (ref "R4") (pin "1") (pinfunction "1_1") (pintype "passive"))
      (node (ref "R47") (pin "2") (pinfunction "2_2") (pintype "passive"))
      (node (ref "T1") (pin "2") (pinfunction "S_2") (pintype "passive"))
      (node (ref "U1") (pin "P46") (pinfunction "IO_L28P_5D7_P46") (pintype "bidirectional"))
    )
    (net (code "67") (name "/PS2DAT") (class "Default")
      (node (ref "R51") (pin "2") (pinfunction "2_2") (pintype "passive"))
      (node (ref "R6") (pin "1") (pinfunction "1_1") (pintype "passive"))
      (node (ref "T3") (pin "2") (pinfunction "S_2") (pintype "passive"))
      (node (ref "U1") (pin "P44") (pinfunction "IOVREF_5_P44") (pintype "bidirectional"))
    )
    (net (code "68") (name "/R0") (class "Default")
      (node (ref "R10") (pin "1") (pinfunction "1_1") (pintype "passive"))
      (node (ref "U1") (pin "P55") (pinfunction "IO_L32P_4GCLK0_P55") (pintype "bidirectional"))
    )
    (net (code "69") (name "/R1") (class "Default")
      (node (ref "R9") (pin "1") (pinfunction "1_1") (pintype "passive"))
      (node (ref "U1") (pin "P53") (pinfunction "IO_L32N_5GCLK3_P53") (pintype "bidirectional"))
    )
    (net (code "70") (name "/SCART_BLANKING") (class "Default")
      (node (ref "R50") (pin "1") (pinfunction "1_1") (pintype "passive"))
      (node (ref "X1") (pin "16") (pinfunction "16_16") (pintype "passive"))
    )
    (net (code "71") (name "/SCART_BLUE") (class "Default")
      (node (ref "R31") (pin "1") (pinfunction "1_1") (pintype "passive"))
      (node (ref "R32") (pin "1") (pinfunction "1_1") (pintype "passive"))
      (node (ref "R33") (pin "1") (pinfunction "1_1") (pintype "passive"))
      (node (ref "X1") (pin "7") (pinfunction "7_7") (pintype "passive"))
    )
    (net (code "72") (name "/SCART_COMP") (class "Default")
      (node (ref "R13") (pin "1") (pinfunction "1_1") (pintype "passive"))
      (node (ref "R14") (pin "1") (pinfunction "1_1") (pintype "passive"))
      (node (ref "X1") (pin "19") (pinfunction "19_19") (pintype "passive"))
    )
    (net (code "73") (name "/SCART_GREEN") (class "Default")
      (node (ref "R26") (pin "1") (pinfunction "1_1") (pintype "passive"))
      (node (ref "R27") (pin "1") (pinfunction "1_1") (pintype "passive"))
      (node (ref "R28") (pin "1") (pinfunction "1_1") (pintype "passive"))
      (node (ref "X1") (pin "11") (pinfunction "11_11") (pintype "passive"))
    )
    (net (code "74") (name "/SCART_LEFT") (class "Default")
      (node (ref "C3") (pin "2") (pinfunction "2_2") (pintype "passive"))
      (node (ref "X1") (pin "3") (pinfunction "3_3") (pintype "passive"))
    )
    (net (code "75") (name "/SCART_MODE") (class "Default")
      (node (ref "X1") (pin "8") (pinfunction "8_8") (pintype "passive"))
    )
    (net (code "76") (name "/SCART_RED") (class "Default")
      (node (ref "R15") (pin "1") (pinfunction "1_1") (pintype "passive"))
      (node (ref "R16") (pin "1") (pinfunction "1_1") (pintype "passive"))
      (node (ref "R20") (pin "1") (pinfunction "1_1") (pintype "passive"))
      (node (ref "X1") (pin "15") (pinfunction "15_15") (pintype "passive"))
    )
    (net (code "77") (name "/SCART_RIGHT") (class "Default")
      (node (ref "C4") (pin "2") (pinfunction "2_2") (pintype "passive"))
      (node (ref "X1") (pin "1") (pinfunction "1_1") (pintype "passive"))
    )
    (net (code "78") (name "/SD_CLK") (class "Default")
      (node (ref "U$3") (pin "5") (pinfunction "SCLK_5") (pintype "input"))
      (node (ref "U1") (pin "P41") (pinfunction "IO_L01N_5RDWR_B_P41") (pintype "bidirectional"))
    )
    (net (code "79") (name "/SD_CS") (class "Default")
      (node (ref "U$3") (pin "1") (pinfunction "CS_1") (pintype "input"))
      (node (ref "U1") (pin "P141") (pinfunction "IO_L01N_0VRP_0_P141") (pintype "bidirectional"))
    )
    (net (code "80") (name "/SD_DI") (class "Default")
      (node (ref "U$3") (pin "2") (pinfunction "DATA_IN_2") (pintype "input"))
      (node (ref "U1") (pin "P140") (pinfunction "IO_L01P_0VRN_0_P140") (pintype "bidirectional"))
    )
    (net (code "81") (name "/SD_DO") (class "Default")
      (node (ref "U$3") (pin "7") (pinfunction "DATA_OUT_7") (pintype "output"))
      (node (ref "U1") (pin "P40") (pinfunction "IO_L01P_5CS_B_P40") (pintype "bidirectional"))
    )
    (net (code "82") (name "/SPI_MISO") (class "Default")
      (node (ref "IC3") (pin "17") (pinfunction "PB3(PDO/MISO/PCINT3)_17") (pintype "bidirectional"))
      (node (ref "SV1") (pin "16") (pinfunction "16_16") (pintype "passive"))
    )
    (net (code "83") (name "/SPI_MOSI") (class "Default")
      (node (ref "IC3") (pin "16") (pinfunction "PB2(PDI/MOSI/PCINT2)_16") (pintype "bidirectional"))
      (node (ref "SV1") (pin "20") (pinfunction "20_20") (pintype "passive"))
    )
    (net (code "84") (name "/SPI_SCLK") (class "Default")
      (node (ref "IC3") (pin "15") (pinfunction "PB1(SCK/PCINT1)_15") (pintype "bidirectional"))
      (node (ref "SV1") (pin "18") (pinfunction "18_18") (pintype "passive"))
    )
    (net (code "85") (name "/SPI_SEL") (class "Default")
      (node (ref "IC3") (pin "14") (pinfunction "PB0(SS/PCINT0)_14") (pintype "bidirectional"))
      (node (ref "SV1") (pin "14") (pinfunction "14_14") (pintype "passive"))
    )
    (net (code "86") (name "/SRAM_A0") (class "Default")
      (node (ref "U$6") (pin "P20") (pinfunction "A0_P20") (pintype "bidirectional"))
      (node (ref "U1") (pin "P24") (pinfunction "IO_L24N_6VREF_6_P24") (pintype "bidirectional"))
    )
    (net (code "87") (name "/SRAM_A1") (class "Default")
      (node (ref "U$6") (pin "P19") (pinfunction "A1_P19") (pintype "bidirectional"))
      (node (ref "U1") (pin "P23") (pinfunction "IO_L24P_6_P23") (pintype "bidirectional"))
    )
    (net (code "88") (name "/SRAM_A2") (class "Default")
      (node (ref "U$6") (pin "P18") (pinfunction "A2_P18") (pintype "bidirectional"))
      (node (ref "U1") (pin "P21") (pinfunction "IO_L40N_6_P21") (pintype "bidirectional"))
    )
    (net (code "89") (name "/SRAM_A3") (class "Default")
      (node (ref "U$6") (pin "P17") (pinfunction "A3_P17") (pintype "bidirectional"))
      (node (ref "U1") (pin "P20") (pinfunction "IO_L40P_6VREF_6_P20") (pintype "bidirectional"))
    )
    (net (code "90") (name "/SRAM_A4") (class "Default")
      (node (ref "U$6") (pin "P16") (pinfunction "A4_P16") (pintype "bidirectional"))
      (node (ref "U1") (pin "P18") (pinfunction "IO_L40N_7VREF_7_P18") (pintype "bidirectional"))
    )
    (net (code "91") (name "/SRAM_A5") (class "Default")
      (node (ref "U$6") (pin "P15") (pinfunction "A5_P15") (pintype "bidirectional"))
      (node (ref "U1") (pin "P17") (pinfunction "IO_L40P_7_P17") (pintype "bidirectional"))
    )
    (net (code "92") (name "/SRAM_A6") (class "Default")
      (node (ref "U$6") (pin "P14") (pinfunction "A6_P14") (pintype "bidirectional"))
      (node (ref "U1") (pin "P15") (pinfunction "IO_L24N_7_P15") (pintype "bidirectional"))
    )
    (net (code "93") (name "/SRAM_A7") (class "Default")
      (node (ref "U$6") (pin "P13") (pinfunction "A7_P13") (pintype "bidirectional"))
      (node (ref "U1") (pin "P14") (pinfunction "IO_L24P_7_P14") (pintype "bidirectional"))
    )
    (net (code "94") (name "/SRAM_A8") (class "Default")
      (node (ref "U$6") (pin "P3") (pinfunction "A8_P3") (pintype "bidirectional"))
      (node (ref "U1") (pin "P4") (pinfunction "IOVREF_7_P4") (pintype "bidirectional"))
    )
    (net (code "95") (name "/SRAM_A9") (class "Default")
      (node (ref "U$6") (pin "P2") (pinfunction "A9_P2") (pintype "bidirectional"))
      (node (ref "U1") (pin "P2") (pinfunction "IO_L01N_7VRP_7_P2") (pintype "bidirectional"))
    )
    (net (code "96") (name "/SRAM_A10") (class "Default")
      (node (ref "U$6") (pin "P31") (pinfunction "A10_P31") (pintype "bidirectional"))
      (node (ref "U1") (pin "P35") (pinfunction "IO_L01P_6VRN_6_P35") (pintype "bidirectional"))
    )
    (net (code "97") (name "/SRAM_A11") (class "Default")
      (node (ref "U$6") (pin "P1") (pinfunction "A11_P1") (pintype "bidirectional"))
      (node (ref "U1") (pin "P1") (pinfunction "IO_L01P_7VRN_7_P1") (pintype "bidirectional"))
    )
    (net (code "98") (name "/SRAM_A12") (class "Default")
      (node (ref "U$6") (pin "P12") (pinfunction "A12_P12") (pintype "bidirectional"))
      (node (ref "U1") (pin "P13") (pinfunction "IO_L23N_7_P13") (pintype "bidirectional"))
    )
    (net (code "99") (name "/SRAM_A13") (class "Default")
      (node (ref "U$6") (pin "P4") (pinfunction "A13_P4") (pintype "bidirectional"))
      (node (ref "U1") (pin "P5") (pinfunction "IO_L20P_7_P5") (pintype "bidirectional"))
    )
    (net (code "100") (name "/SRAM_A14") (class "Default")
      (node (ref "U$6") (pin "P11") (pinfunction "A14_P11") (pintype "bidirectional"))
      (node (ref "U1") (pin "P12") (pinfunction "IO_L23P_7_P12") (pintype "bidirectional"))
    )
    (net (code "101") (name "/SRAM_A15") (class "Default")
      (node (ref "U$6") (pin "P7") (pinfunction "A15_P7") (pintype "bidirectional"))
      (node (ref "U1") (pin "P8") (pinfunction "IO_L21N_7_P8") (pintype "bidirectional"))
    )
    (net (code "102") (name "/SRAM_A16") (class "Default")
      (node (ref "U$6") (pin "P10") (pinfunction "A16_P10") (pintype "bidirectional"))
      (node (ref "U1") (pin "P11") (pinfunction "IO_L22N_7_P11") (pintype "bidirectional"))
    )
    (net (code "103") (name "/SRAM_A17") (class "Default")
      (node (ref "U$6") (pin "P6") (pinfunction "A17_P6") (pintype "bidirectional"))
      (node (ref "U1") (pin "P7") (pinfunction "IO_L21P_7_P7") (pintype "bidirectional"))
    )
    (net (code "104") (name "/SRAM_A18") (class "Default")
      (node (ref "U$6") (pin "P9") (pinfunction "A18_P9") (pintype "bidirectional"))
      (node (ref "U1") (pin "P10") (pinfunction "IO_L22P_7_P10") (pintype "bidirectional"))
    )
    (net (code "105") (name "/SRAM_D0") (class "Default")
      (node (ref "U$6") (pin "P21") (pinfunction "DQ0_P21") (pintype "bidirectional"))
      (node (ref "U1") (pin "P25") (pinfunction "IO_L23P_6_P25") (pintype "bidirectional"))
    )
    (net (code "106") (name "/SRAM_D1") (class "Default")
      (node (ref "U$6") (pin "P22") (pinfunction "DQ1_P22") (pintype "bidirectional"))
      (node (ref "U1") (pin "P26") (pinfunction "IO_L23N_6_P26") (pintype "bidirectional"))
    )
    (net (code "107") (name "/SRAM_D2") (class "Default")
      (node (ref "U$6") (pin "P23") (pinfunction "DQ2_P23") (pintype "bidirectional"))
      (node (ref "U1") (pin "P27") (pinfunction "IO_L22P_6_P27") (pintype "bidirectional"))
    )
    (net (code "108") (name "/SRAM_D3") (class "Default")
      (node (ref "U$6") (pin "P25") (pinfunction "DQ3_P25") (pintype "bidirectional"))
      (node (ref "U1") (pin "P28") (pinfunction "IO_L22N_6_P28") (pintype "bidirectional"))
    )
    (net (code "109") (name "/SRAM_D4") (class "Default")
      (node (ref "U$6") (pin "P26") (pinfunction "DQ4_P26") (pintype "bidirectional"))
      (node (ref "U1") (pin "P30") (pinfunction "IO_L21P_6_P30") (pintype "bidirectional"))
    )
    (net (code "110") (name "/SRAM_D5") (class "Default")
      (node (ref "U$6") (pin "P27") (pinfunction "DQ5_P27") (pintype "bidirectional"))
      (node (ref "U1") (pin "P31") (pinfunction "IO_L21N_6_P31") (pintype "bidirectional"))
    )
    (net (code "111") (name "/SRAM_D6") (class "Default")
      (node (ref "U$6") (pin "P28") (pinfunction "DQ6_P28") (pintype "bidirectional"))
      (node (ref "U1") (pin "P32") (pinfunction "IO_L20P_6_P32") (pintype "bidirectional"))
    )
    (net (code "112") (name "/SRAM_D7") (class "Default")
      (node (ref "U$6") (pin "P29") (pinfunction "DQ7_P29") (pintype "bidirectional"))
      (node (ref "U1") (pin "P33") (pinfunction "IO_L20N_6_P33") (pintype "bidirectional"))
    )
    (net (code "113") (name "/SRAM_OE") (class "Default")
      (node (ref "U$6") (pin "P32") (pinfunction "OE_P32") (pintype "bidirectional"))
      (node (ref "U1") (pin "P36") (pinfunction "IO_L01N_6VRP_6_P36") (pintype "bidirectional"))
    )
    (net (code "114") (name "/SRAM_WE") (class "Default")
      (node (ref "U$6") (pin "P5") (pinfunction "WE_P5") (pintype "bidirectional"))
      (node (ref "U1") (pin "P6") (pinfunction "IO_L20N_7_P6") (pintype "bidirectional"))
    )
    (net (code "115") (name "/TCK") (class "Default")
      (node (ref "IC1") (pin "6") (pinfunction "TCK_6") (pintype "bidirectional"))
      (node (ref "IC3") (pin "19") (pinfunction "PB5(PCINT5)_19") (pintype "bidirectional"))
      (node (ref "R2") (pin "2") (pinfunction "2_2") (pintype "passive"))
      (node (ref "SV1") (pin "9") (pinfunction "9_9") (pintype "passive"))
    )
    (net (code "116") (name "/TDI_FPGA") (class "Default")
      (node (ref "IC3") (pin "21") (pinfunction "PB7(OC0A/OC1C/PCINT7)_21") (pintype "bidirectional"))
      (node (ref "R1") (pin "2") (pinfunction "2_2") (pintype "passive"))
      (node (ref "SV1") (pin "7") (pinfunction "7_7") (pintype "passive"))
    )
    (net (code "117") (name "/TDO_EXP") (class "Default")
      (node (ref "IC3") (pin "23") (pinfunction "PC6(OC1A/PCINT8)_23") (pintype "bidirectional"))
      (node (ref "SV1") (pin "8") (pinfunction "8_8") (pintype "passive"))
    )
    (net (code "118") (name "/TDO_PROM") (class "Default")
      (node (ref "IC1") (pin "17") (pinfunction "TDO_17") (pintype "bidirectional"))
      (node (ref "IC3") (pin "20") (pinfunction "PB6(PCINT6)_20") (pintype "bidirectional"))
      (node (ref "SV1") (pin "10") (pinfunction "10_10") (pintype "passive"))
    )
    (net (code "119") (name "/TMS") (class "Default")
      (node (ref "IC1") (pin "5") (pinfunction "TMS_5") (pintype "bidirectional"))
      (node (ref "IC3") (pin "18") (pinfunction "PB4(T1/PCINT4)_18") (pintype "bidirectional"))
      (node (ref "R3") (pin "2") (pinfunction "2_2") (pintype "passive"))
      (node (ref "SV1") (pin "12") (pinfunction "12_12") (pintype "passive"))
    )
    (net (code "120") (name "/VCC") (class "Default")
      (node (ref "C10") (pin "1") (pinfunction "1_1") (pintype "passive"))
      (node (ref "C11") (pin "1") (pinfunction "1_1") (pintype "passive"))
      (node (ref "C12") (pin "1") (pinfunction "1_1") (pintype "passive"))
      (node (ref "C13") (pin "1") (pinfunction "1_1") (pintype "passive"))
      (node (ref "C14") (pin "1") (pinfunction "1_1") (pintype "passive"))
      (node (ref "C15") (pin "1") (pinfunction "1_1") (pintype "passive"))
      (node (ref "C16") (pin "1") (pinfunction "1_1") (pintype "passive"))
      (node (ref "C17") (pin "1") (pinfunction "1_1") (pintype "passive"))
      (node (ref "C26") (pin "1") (pinfunction "1_1") (pintype "passive"))
      (node (ref "C27") (pin "1") (pinfunction "1_1") (pintype "passive"))
      (node (ref "C29") (pin "1") (pinfunction "1_1") (pintype "passive"))
      (node (ref "C34") (pin "1") (pinfunction "1_1") (pintype "passive"))
      (node (ref "C39") (pin "+") (pinfunction "+_+") (pintype "passive"))
      (node (ref "C6") (pin "1") (pinfunction "1_1") (pintype "passive"))
      (node (ref "C7") (pin "1") (pinfunction "1_1") (pintype "passive"))
      (node (ref "C8") (pin "1") (pinfunction "1_1") (pintype "passive"))
      (node (ref "C9") (pin "1") (pinfunction "1_1") (pintype "passive"))
      (node (ref "IC1") (pin "18") (pinfunction "VCCINT_18") (pintype "bidirectional"))
      (node (ref "IC1") (pin "19") (pinfunction "VCCO_19") (pintype "bidirectional"))
      (node (ref "IC1") (pin "20") (pinfunction "VCCJ_20") (pintype "bidirectional"))
      (node (ref "IC2") (pin "8") (pinfunction "VCC_8") (pintype "power_in"))
      (node (ref "IC3") (pin "31") (pinfunction "UVCC_31") (pintype "bidirectional"))
      (node (ref "IC3") (pin "32") (pinfunction "AVCC_32") (pintype "bidirectional"))
      (node (ref "IC3") (pin "4") (pinfunction "VCC_4") (pintype "bidirectional"))
      (node (ref "Q5") (pin "3") (pinfunction "C_3") (pintype "passive"))
      (node (ref "Q6") (pin "3") (pinfunction "C_3") (pintype "passive"))
      (node (ref "Q7") (pin "3") (pinfunction "C_3") (pintype "passive"))
      (node (ref "Q8") (pin "3") (pinfunction "C_3") (pintype "passive"))
      (node (ref "R11") (pin "1") (pinfunction "1_1") (pintype "passive"))
      (node (ref "R22") (pin "1") (pinfunction "1_1") (pintype "passive"))
      (node (ref "R35") (pin "2") (pinfunction "2_2") (pintype "passive"))
      (node (ref "R36") (pin "2") (pinfunction "2_2") (pintype "passive"))
      (node (ref "R37") (pin "2") (pinfunction "2_2") (pintype "passive"))
      (node (ref "R38") (pin "2") (pinfunction "2_2") (pintype "passive"))
      (node (ref "R39") (pin "2") (pinfunction "2_2") (pintype "passive"))
      (node (ref "R4") (pin "2") (pinfunction "2_2") (pintype "passive"))
      (node (ref "R40") (pin "1") (pinfunction "1_1") (pintype "passive"))
      (node (ref "R41") (pin "1") (pinfunction "1_1") (pintype "passive"))
      (node (ref "R42") (pin "1") (pinfunction "1_1") (pintype "passive"))
      (node (ref "R43") (pin "1") (pinfunction "1_1") (pintype "passive"))
      (node (ref "R44") (pin "1") (pinfunction "1_1") (pintype "passive"))
      (node (ref "R45") (pin "1") (pinfunction "1_1") (pintype "passive"))
      (node (ref "R46") (pin "2") (pinfunction "2_2") (pintype "passive"))
      (node (ref "R55") (pin "1") (pinfunction "1_1") (pintype "passive"))
      (node (ref "R56") (pin "1") (pinfunction "1_1") (pintype "passive"))
      (node (ref "R6") (pin "2") (pinfunction "2_2") (pintype "passive"))
      (node (ref "REG3.3") (pin "4") (pinfunction "VOUT1_4") (pintype "bidirectional"))
      (node (ref "SV1") (pin "3") (pinfunction "3_3") (pintype "passive"))
      (node (ref "SV1") (pin "4") (pinfunction "4_4") (pintype "passive"))
      (node (ref "SV2") (pin "4") (pinfunction "4_4") (pintype "passive"))
      (node (ref "SV2") (pin "6") (pinfunction "6_6") (pintype "passive"))
      (node (ref "SV3") (pin "1") (pinfunction "1_1") (pintype "passive"))
      (node (ref "SV5") (pin "7") (pinfunction "7_7") (pintype "passive"))
      (node (ref "SV5") (pin "8") (pinfunction "8_8") (pintype "passive"))
      (node (ref "T1") (pin "3") (pinfunction "G_3") (pintype "passive"))
      (node (ref "T2") (pin "3") (pinfunction "C_3") (pintype "passive"))
      (node (ref "T3") (pin "3") (pinfunction "G_3") (pintype "passive"))
      (node (ref "U$2") (pin "VDD") (pinfunction "VDD_VDD") (pintype "power_in"))
      (node (ref "U$3") (pin "4") (pinfunction "VDD_4") (pintype "power_in"))
      (node (ref "U$6") (pin "P8") (pinfunction "VCC_P8") (pintype "bidirectional"))
      (node (ref "U1") (pin "P106") (pinfunction "VCCO_RIGHT2_P106") (pintype "passive"))
      (node (ref "U1") (pin "P115") (pinfunction "VCCO_TOP0_P115") (pintype "passive"))
      (node (ref "U1") (pin "P126") (pinfunction "VCCO_TOP1_P126") (pintype "passive"))
      (node (ref "U1") (pin "P138") (pinfunction "VCCO_TOP2_P138") (pintype "passive"))
      (node (ref "U1") (pin "P19") (pinfunction "VCCO_LEFT1_P19") (pintype "passive"))
      (node (ref "U1") (pin "P3") (pinfunction "VCCO_LEFT0_P3") (pintype "passive"))
      (node (ref "U1") (pin "P34") (pinfunction "VCCO_LEFT2_P34") (pintype "passive"))
      (node (ref "U1") (pin "P43") (pinfunction "VCCO_BOTTOM0_P43") (pintype "passive"))
      (node (ref "U1") (pin "P54") (pinfunction "VCCO_BOTTOM1_P54") (pintype "passive"))
      (node (ref "U1") (pin "P66") (pinfunction "VCCO_BOTTOM2_P66") (pintype "passive"))
      (node (ref "U1") (pin "P75") (pinfunction "VCCO_RIGHT0_P75") (pintype "passive"))
      (node (ref "U1") (pin "P91") (pinfunction "VCCO_RIGHT1_P91") (pintype "passive"))
    )
    (net (code "121") (name "/VCC5") (class "Default")
      (node (ref "C33") (pin "+") (pinfunction "+_+") (pintype "passive"))
      (node (ref "PWR_HDR") (pin "2") (pinfunction "2_2") (pintype "passive"))
      (node (ref "R5") (pin "2") (pinfunction "2_2") (pintype "passive"))
      (node (ref "R7") (pin "2") (pinfunction "2_2") (pintype "passive"))
      (node (ref "REG1.2") (pin "3") (pinfunction "VCC_3") (pintype "bidirectional"))
      (node (ref "REG2.5") (pin "3") (pinfunction "VCC_3") (pintype "bidirectional"))
      (node (ref "REG3.3") (pin "3") (pinfunction "VCC_3") (pintype "bidirectional"))
      (node (ref "SV5") (pin "10") (pinfunction "10_10") (pintype "passive"))
      (node (ref "SV5") (pin "9") (pinfunction "9_9") (pintype "passive"))
      (node (ref "X3") (pin "5") (pinfunction "5_5") (pintype "passive"))
      (node (ref "X7") (pin "2") (pinfunction "2_2") (pintype "power_in"))
    )
    (net (code "122") (name "/VCCAUX") (class "Default")
      (node (ref "C18") (pin "1") (pinfunction "1_1") (pintype "passive"))
      (node (ref "C19") (pin "1") (pinfunction "1_1") (pintype "passive"))
      (node (ref "C20") (pin "1") (pinfunction "1_1") (pintype "passive"))
      (node (ref "C21") (pin "1") (pinfunction "1_1") (pintype "passive"))
      (node (ref "C40") (pin "+") (pinfunction "+_+") (pintype "passive"))
      (node (ref "R50") (pin "2") (pinfunction "2_2") (pintype "passive"))
      (node (ref "REG2.5") (pin "4") (pinfunction "VOUT1_4") (pintype "bidirectional"))
      (node (ref "SV5") (pin "2") (pinfunction "2_2") (pintype "passive"))
      (node (ref "U1") (pin "P120") (pinfunction "VCCAUX2_P120") (pintype "passive"))
      (node (ref "U1") (pin "P134") (pinfunction "VCCAUX3_P134") (pintype "passive"))
      (node (ref "U1") (pin "P48") (pinfunction "VCCAUX0_P48") (pintype "passive"))
      (node (ref "U1") (pin "P62") (pinfunction "VCCAUX1_P62") (pintype "passive"))
    )
    (net (code "123") (name "/VCCINT") (class "Default")
      (node (ref "C22") (pin "1") (pinfunction "1_1") (pintype "passive"))
      (node (ref "C23") (pin "1") (pinfunction "1_1") (pintype "passive"))
      (node (ref "C24") (pin "1") (pinfunction "1_1") (pintype "passive"))
      (node (ref "C25") (pin "1") (pinfunction "1_1") (pintype "passive"))
      (node (ref "C42") (pin "+") (pinfunction "+_+") (pintype "passive"))
      (node (ref "REG1.2") (pin "4") (pinfunction "VOUT1_4") (pintype "bidirectional"))
      (node (ref "SV5") (pin "1") (pinfunction "1_1") (pintype "passive"))
      (node (ref "U1") (pin "P121") (pinfunction "VCCINT2_P121") (pintype "passive"))
      (node (ref "U1") (pin "P133") (pinfunction "VCCINT3_P133") (pintype "passive"))
      (node (ref "U1") (pin "P49") (pinfunction "VCCINT0_P49") (pintype "passive"))
      (node (ref "U1") (pin "P61") (pinfunction "VCCINT1_P61") (pintype "passive"))
    )
    (net (code "124") (name "/X3") (class "Default")
      (node (ref "SV2") (pin "5") (pinfunction "5_5") (pintype "passive"))
      (node (ref "U1") (pin "P76") (pinfunction "IO_P76") (pintype "bidirectional"))
    )
    (net (code "125") (name "/X4") (class "Default")
      (node (ref "SV2") (pin "3") (pinfunction "3_3") (pintype "passive"))
      (node (ref "U1") (pin "P77") (pinfunction "IO_L20P_3_P77") (pintype "bidirectional"))
    )
    (net (code "126") (name "/X8") (class "Default")
      (node (ref "SV2") (pin "1") (pinfunction "1_1") (pintype "passive"))
      (node (ref "U1") (pin "P74") (pinfunction "IO_L01N_3VRP_3_P74") (pintype "bidirectional"))
    )
    (net (code "127") (name "GND") (class "Default")
      (node (ref "C1") (pin "1") (pinfunction "1_1") (pintype "passive"))
      (node (ref "C10") (pin "2") (pinfunction "2_2") (pintype "passive"))
      (node (ref "C11") (pin "2") (pinfunction "2_2") (pintype "passive"))
      (node (ref "C12") (pin "2") (pinfunction "2_2") (pintype "passive"))
      (node (ref "C13") (pin "2") (pinfunction "2_2") (pintype "passive"))
      (node (ref "C14") (pin "2") (pinfunction "2_2") (pintype "passive"))
      (node (ref "C15") (pin "2") (pinfunction "2_2") (pintype "passive"))
      (node (ref "C16") (pin "2") (pinfunction "2_2") (pintype "passive"))
      (node (ref "C17") (pin "2") (pinfunction "2_2") (pintype "passive"))
      (node (ref "C18") (pin "2") (pinfunction "2_2") (pintype "passive"))
      (node (ref "C19") (pin "2") (pinfunction "2_2") (pintype "passive"))
      (node (ref "C20") (pin "2") (pinfunction "2_2") (pintype "passive"))
      (node (ref "C21") (pin "2") (pinfunction "2_2") (pintype "passive"))
      (node (ref "C22") (pin "2") (pinfunction "2_2") (pintype "passive"))
      (node (ref "C23") (pin "2") (pinfunction "2_2") (pintype "passive"))
      (node (ref "C24") (pin "2") (pinfunction "2_2") (pintype "passive"))
      (node (ref "C25") (pin "2") (pinfunction "2_2") (pintype "passive"))
      (node (ref "C26") (pin "2") (pinfunction "2_2") (pintype "passive"))
      (node (ref "C27") (pin "2") (pinfunction "2_2") (pintype "passive"))
      (node (ref "C29") (pin "2") (pinfunction "2_2") (pintype "passive"))
      (node (ref "C33") (pin "-") (pinfunction "-_-") (pintype "passive"))
      (node (ref "C34") (pin "2") (pinfunction "2_2") (pintype "passive"))
      (node (ref "C37") (pin "1") (pinfunction "1_1") (pintype "passive"))
      (node (ref "C38") (pin "1") (pinfunction "1_1") (pintype "passive"))
      (node (ref "C39") (pin "-") (pinfunction "-_-") (pintype "passive"))
      (node (ref "C40") (pin "-") (pinfunction "-_-") (pintype "passive"))
      (node (ref "C41") (pin "2") (pinfunction "2_2") (pintype "passive"))
      (node (ref "C42") (pin "-") (pinfunction "-_-") (pintype "passive"))
      (node (ref "C5") (pin "1") (pinfunction "1_1") (pintype "passive"))
      (node (ref "C6") (pin "2") (pinfunction "2_2") (pintype "passive"))
      (node (ref "C7") (pin "2") (pinfunction "2_2") (pintype "passive"))
      (node (ref "C8") (pin "2") (pinfunction "2_2") (pintype "passive"))
      (node (ref "C9") (pin "2") (pinfunction "2_2") (pintype "passive"))
      (node (ref "IC1") (pin "11") (pinfunction "GND_11") (pintype "bidirectional"))
      (node (ref "IC2") (pin "4") (pinfunction "GND_4") (pintype "power_in"))
      (node (ref "IC3") (pin "3") (pinfunction "GND_3") (pintype "bidirectional"))
      (node (ref "LED1") (pin "C") (pinfunction "C_C") (pintype "passive"))
      (node (ref "PWR_HDR") (pin "1") (pinfunction "1_1") (pintype "passive"))
      (node (ref "R17") (pin "1") (pinfunction "1_1") (pintype "passive"))
      (node (ref "R19") (pin "1") (pinfunction "1_1") (pintype "passive"))
      (node (ref "R21") (pin "1") (pinfunction "1_1") (pintype "passive"))
      (node (ref "REG1.2") (pin "1") (pinfunction "GND_1") (pintype "bidirectional"))
      (node (ref "REG2.5") (pin "1") (pinfunction "GND_1") (pintype "bidirectional"))
      (node (ref "REG3.3") (pin "1") (pinfunction "GND_1") (pintype "bidirectional"))
      (node (ref "SV1") (pin "5") (pinfunction "5_5") (pintype "passive"))
      (node (ref "SV1") (pin "6") (pinfunction "6_6") (pintype "passive"))
      (node (ref "SV2") (pin "2") (pinfunction "2_2") (pintype "passive"))
      (node (ref "SV3") (pin "2") (pinfunction "2_2") (pintype "passive"))
      (node (ref "SV5") (pin "3") (pinfunction "3_3") (pintype "passive"))
      (node (ref "U$1") (pin "GND") (pinfunction "GND_GND") (pintype "bidirectional"))
      (node (ref "U$2") (pin "GND") (pinfunction "GND_GND") (pintype "power_in"))
      (node (ref "U$3") (pin "3") (pinfunction "VSS1_3") (pintype "power_in"))
      (node (ref "U$3") (pin "6") (pinfunction "VSS2_6") (pintype "power_in"))
      (node (ref "U$3") (pin "MT1") (pinfunction "COMMON_SW_MT1") (pintype "passive"))
      (node (ref "U$3") (pin "MT3") (pinfunction "GND_MT3") (pintype "power_in"))
      (node (ref "U$6") (pin "P24") (pinfunction "VSS_P24") (pintype "bidirectional"))
      (node (ref "U$6") (pin "P30") (pinfunction "CE_P30") (pintype "bidirectional"))
      (node (ref "U$7") (pin "GND") (pinfunction "GND_GND") (pintype "bidirectional"))
      (node (ref "U$8") (pin "GND") (pinfunction "GND_GND") (pintype "bidirectional"))
      (node (ref "U$9") (pin "GND") (pinfunction "GND_GND") (pintype "bidirectional"))
      (node (ref "U1") (pin "P101") (pinfunction "GND11_P101") (pintype "passive"))
      (node (ref "U1") (pin "P114") (pinfunction "GND12_P114") (pintype "passive"))
      (node (ref "U1") (pin "P117") (pinfunction "GND13_P117") (pintype "passive"))
      (node (ref "U1") (pin "P136") (pinfunction "GND14_P136") (pintype "passive"))
      (node (ref "U1") (pin "P139") (pinfunction "GND15_P139") (pintype "passive"))
      (node (ref "U1") (pin "P16") (pinfunction "GND1_P16") (pintype "passive"))
      (node (ref "U1") (pin "P22") (pinfunction "GND2_P22") (pintype "passive"))
      (node (ref "U1") (pin "P29") (pinfunction "GND3_P29") (pintype "passive"))
      (node (ref "U1") (pin "P37") (pinfunction "M1_P37") (pintype "bidirectional"))
      (node (ref "U1") (pin "P38") (pinfunction "M0_P38") (pintype "bidirectional"))
      (node (ref "U1") (pin "P39") (pinfunction "M2_P39") (pintype "bidirectional"))
      (node (ref "U1") (pin "P42") (pinfunction "GND4_P42") (pintype "passive"))
      (node (ref "U1") (pin "P45") (pinfunction "GND5_P45") (pintype "passive"))
      (node (ref "U1") (pin "P64") (pinfunction "GND6_P64") (pintype "passive"))
      (node (ref "U1") (pin "P67") (pinfunction "GND7_P67") (pintype "passive"))
      (node (ref "U1") (pin "P81") (pinfunction "GND8_P81") (pintype "passive"))
      (node (ref "U1") (pin "P88") (pinfunction "GND9_P88") (pintype "passive"))
      (node (ref "U1") (pin "P9") (pinfunction "GND0_P9") (pintype "passive"))
      (node (ref "U1") (pin "P94") (pinfunction "GND10_P94") (pintype "passive"))
      (node (ref "X1") (pin "13") (pinfunction "13_13") (pintype "passive"))
      (node (ref "X1") (pin "14") (pinfunction "14_14") (pintype "passive"))
      (node (ref "X1") (pin "17") (pinfunction "17_17") (pintype "passive"))
      (node (ref "X1") (pin "18") (pinfunction "18_18") (pintype "passive"))
      (node (ref "X1") (pin "21") (pinfunction "21_21") (pintype "passive"))
      (node (ref "X1") (pin "4") (pinfunction "4_4") (pintype "passive"))
      (node (ref "X1") (pin "5") (pinfunction "5_5") (pintype "passive"))
      (node (ref "X1") (pin "9") (pinfunction "9_9") (pintype "passive"))
      (node (ref "X3") (pin "3") (pinfunction "3_3") (pintype "passive"))
      (node (ref "X3") (pin "SH1") (pinfunction "PE1_SH1") (pintype "power_in"))
      (node (ref "X3") (pin "SH2") (pinfunction "PE2_SH2") (pintype "power_in"))
      (node (ref "X3") (pin "SH3") (pinfunction "PE3_SH3") (pintype "power_in"))
      (node (ref "X4") (pin "8") (pinfunction "F_8") (pintype "passive"))
      (node (ref "X4") (pin "G1") (pinfunction "G1_G1") (pintype "passive"))
      (node (ref "X5") (pin "8") (pinfunction "F_8") (pintype "passive"))
      (node (ref "X5") (pin "G1") (pinfunction "G1_G1") (pintype "passive"))
      (node (ref "X7") (pin "3") (pinfunction "3_3") (pintype "power_in"))
      (node (ref "X8") (pin "1") (pinfunction "1_1") (pintype "passive"))
    )
    (net (code "128") (name "Net-(C1-Pad2)") (class "Default")
      (node (ref "C1") (pin "2") (pinfunction "2_2") (pintype "passive"))
      (node (ref "R23") (pin "2") (pinfunction "2_2") (pintype "passive"))
      (node (ref "R48") (pin "1") (pinfunction "1_1") (pintype "passive"))
    )
    (net (code "129") (name "Net-(C2-Pad1)") (class "Default")
      (node (ref "C2") (pin "1") (pinfunction "1_1") (pintype "passive"))
      (node (ref "R17") (pin "2") (pinfunction "2_2") (pintype "passive"))
      (node (ref "X8") (pin "2") (pinfunction "2_2") (pintype "passive"))
      (node (ref "X8") (pin "3") (pinfunction "3_3") (pintype "passive"))
      (node (ref "X8") (pin "4") (pinfunction "4_4") (pintype "passive"))
      (node (ref "X8") (pin "5") (pinfunction "5_5") (pintype "passive"))
    )
    (net (code "130") (name "Net-(C3-Pad1)") (class "Default")
      (node (ref "C3") (pin "1") (pinfunction "1_1") (pintype "passive"))
      (node (ref "R48") (pin "2") (pinfunction "2_2") (pintype "passive"))
    )
    (net (code "131") (name "Net-(C4-Pad1)") (class "Default")
      (node (ref "C4") (pin "1") (pinfunction "1_1") (pintype "passive"))
      (node (ref "R49") (pin "2") (pinfunction "2_2") (pintype "passive"))
    )
    (net (code "132") (name "Net-(C5-Pad2)") (class "Default")
      (node (ref "C5") (pin "2") (pinfunction "2_2") (pintype "passive"))
      (node (ref "R34") (pin "2") (pinfunction "2_2") (pintype "passive"))
      (node (ref "R49") (pin "1") (pinfunction "1_1") (pintype "passive"))
    )
    (net (code "133") (name "Net-(C38-Pad2)") (class "Default")
      (node (ref "C38") (pin "2") (pinfunction "2_2") (pintype "passive"))
      (node (ref "JP2") (pin "1") (pinfunction "1_1") (pintype "passive"))
      (node (ref "Q1") (pin "2") (pinfunction "2_2") (pintype "passive"))
    )
    (net (code "134") (name "Net-(IC1-CLK)") (class "Default")
      (node (ref "IC1") (pin "3") (pinfunction "CLK_3") (pintype "bidirectional"))
      (node (ref "U1") (pin "P72") (pinfunction "CCLK_P72") (pintype "bidirectional"))
    )
    (net (code "135") (name "Net-(IC1-TDI)") (class "Default")
      (node (ref "IC1") (pin "4") (pinfunction "TDI_4") (pintype "bidirectional"))
      (node (ref "U1") (pin "P109") (pinfunction "TDO_P109") (pintype "bidirectional"))
    )
    (net (code "136") (name "Net-(IC1-{slash}CE)") (class "Default")
      (node (ref "IC1") (pin "10") (pinfunction "/CE_10") (pintype "bidirectional"))
      (node (ref "U1") (pin "P71") (pinfunction "DONE_P71") (pintype "bidirectional"))
    )
    (net (code "137") (name "Net-(IC1-{slash}CF)") (class "Default")
      (node (ref "IC1") (pin "7") (pinfunction "/CF_7") (pintype "bidirectional"))
      (node (ref "U1") (pin "P143") (pinfunction "PROG_B_P143") (pintype "bidirectional"))
    )
    (net (code "138") (name "Net-(IC3-D+)") (class "Default")
      (node (ref "IC3") (pin "29") (pinfunction "D+_29") (pintype "bidirectional"))
      (node (ref "R54") (pin "2") (pinfunction "2_2") (pintype "passive"))
    )
    (net (code "139") (name "Net-(IC3-D-)") (class "Default")
      (node (ref "IC3") (pin "30") (pinfunction "D-_30") (pintype "bidirectional"))
      (node (ref "R53") (pin "2") (pinfunction "2_2") (pintype "passive"))
    )
    (net (code "140") (name "Net-(IC3-UCAP)") (class "Default")
      (node (ref "C41") (pin "1") (pinfunction "1_1") (pintype "passive"))
      (node (ref "IC3") (pin "27") (pinfunction "UCAP_27") (pintype "bidirectional"))
    )
    (net (code "141") (name "Net-(IC3-UGND)") (class "Default")
      (node (ref "IC3") (pin "28") (pinfunction "UGND_28") (pintype "bidirectional"))
      (node (ref "X6") (pin "4") (pinfunction "4_4") (pintype "passive"))
    )
    (net (code "142") (name "Net-(IC3-XTAL1)") (class "Default")
      (node (ref "IC3") (pin "1") (pinfunction "XTAL1_1") (pintype "bidirectional"))
      (node (ref "JP2") (pin "2") (pinfunction "2_2") (pintype "passive"))
    )
    (net (code "143") (name "Net-(IC3-XTAL2{slash}PC0)") (class "Default")
      (node (ref "C37") (pin "2") (pinfunction "2_2") (pintype "passive"))
      (node (ref "IC3") (pin "2") (pinfunction "XTAL2/PC0_2") (pintype "bidirectional"))
      (node (ref "Q1") (pin "1") (pinfunction "1_1") (pintype "passive"))
    )
    (net (code "144") (name "Net-(LED1-PadA)") (class "Default")
      (node (ref "LED1") (pin "A") (pinfunction "A_A") (pintype "passive"))
      (node (ref "R11") (pin "2") (pinfunction "2_2") (pintype "passive"))
    )
    (net (code "145") (name "Net-(Q5-B)") (class "Default")
      (node (ref "Q5") (pin "1") (pinfunction "B_1") (pintype "passive"))
      (node (ref "R8") (pin "2") (pinfunction "2_2") (pintype "passive"))
    )
    (net (code "146") (name "Net-(Q5-E)") (class "Default")
      (node (ref "Q5") (pin "2") (pinfunction "E_2") (pintype "passive"))
      (node (ref "R13") (pin "2") (pinfunction "2_2") (pintype "passive"))
      (node (ref "R14") (pin "2") (pinfunction "2_2") (pintype "passive"))
    )
    (net (code "147") (name "Net-(Q6-B)") (class "Default")
      (node (ref "Q6") (pin "1") (pinfunction "B_1") (pintype "passive"))
      (node (ref "R10") (pin "2") (pinfunction "2_2") (pintype "passive"))
      (node (ref "R9") (pin "2") (pinfunction "2_2") (pintype "passive"))
    )
    (net (code "148") (name "Net-(Q6-E)") (class "Default")
      (node (ref "Q6") (pin "2") (pinfunction "E_2") (pintype "passive"))
      (node (ref "R15") (pin "2") (pinfunction "2_2") (pintype "passive"))
      (node (ref "R16") (pin "2") (pinfunction "2_2") (pintype "passive"))
      (node (ref "R20") (pin "2") (pinfunction "2_2") (pintype "passive"))
    )
    (net (code "149") (name "Net-(Q7-B)") (class "Default")
      (node (ref "Q7") (pin "1") (pinfunction "B_1") (pintype "passive"))
      (node (ref "R29") (pin "2") (pinfunction "2_2") (pintype "passive"))
      (node (ref "R30") (pin "2") (pinfunction "2_2") (pintype "passive"))
    )
    (net (code "150") (name "Net-(Q7-E)") (class "Default")
      (node (ref "Q7") (pin "2") (pinfunction "E_2") (pintype "passive"))
      (node (ref "R31") (pin "2") (pinfunction "2_2") (pintype "passive"))
      (node (ref "R32") (pin "2") (pinfunction "2_2") (pintype "passive"))
      (node (ref "R33") (pin "2") (pinfunction "2_2") (pintype "passive"))
    )
    (net (code "151") (name "Net-(Q8-B)") (class "Default")
      (node (ref "Q8") (pin "1") (pinfunction "B_1") (pintype "passive"))
      (node (ref "R24") (pin "2") (pinfunction "2_2") (pintype "passive"))
      (node (ref "R25") (pin "2") (pinfunction "2_2") (pintype "passive"))
    )
    (net (code "152") (name "Net-(Q8-E)") (class "Default")
      (node (ref "Q8") (pin "2") (pinfunction "E_2") (pintype "passive"))
      (node (ref "R26") (pin "2") (pinfunction "2_2") (pintype "passive"))
      (node (ref "R27") (pin "2") (pinfunction "2_2") (pintype "passive"))
      (node (ref "R28") (pin "2") (pinfunction "2_2") (pintype "passive"))
    )
    (net (code "153") (name "Net-(R18-Pad2)") (class "Default")
      (node (ref "R18") (pin "2") (pinfunction "2_2") (pintype "passive"))
      (node (ref "R22") (pin "2") (pinfunction "2_2") (pintype "passive"))
    )
    (net (code "154") (name "Net-(R53-Pad1)") (class "Default")
      (node (ref "R53") (pin "1") (pinfunction "1_1") (pintype "passive"))
      (node (ref "X6") (pin "2") (pinfunction "2_2") (pintype "passive"))
    )
    (net (code "155") (name "Net-(R54-Pad1)") (class "Default")
      (node (ref "R54") (pin "1") (pinfunction "1_1") (pintype "passive"))
      (node (ref "X6") (pin "3") (pinfunction "3_3") (pintype "passive"))
    )
    (net (code "156") (name "Net-(T2-B)") (class "Default")
      (node (ref "C2") (pin "2") (pinfunction "2_2") (pintype "passive"))
      (node (ref "R18") (pin "1") (pinfunction "1_1") (pintype "passive"))
      (node (ref "R19") (pin "2") (pinfunction "2_2") (pintype "passive"))
      (node (ref "T2") (pin "1") (pinfunction "B_1") (pintype "passive"))
    )
    (net (code "157") (name "Net-(U1N-TCK)") (class "Default")
      (node (ref "R2") (pin "1") (pinfunction "1_1") (pintype "passive"))
      (node (ref "U1") (pin "P110") (pinfunction "TCK_P110") (pintype "bidirectional"))
    )
    (net (code "158") (name "Net-(U1N-TDI)") (class "Default")
      (node (ref "R1") (pin "1") (pinfunction "1_1") (pintype "passive"))
      (node (ref "U1") (pin "P144") (pinfunction "TDI_P144") (pintype "bidirectional"))
    )
    (net (code "159") (name "Net-(U1N-TMS)") (class "Default")
      (node (ref "R3") (pin "1") (pinfunction "1_1") (pintype "passive"))
      (node (ref "U1") (pin "P111") (pinfunction "TMS_P111") (pintype "bidirectional"))
    )
    (net (code "160") (name "unconnected-(IC1-NC.1-Pad2)") (class "Default")
      (node (ref "IC1") (pin "2") (pinfunction "NC.1_2") (pintype "bidirectional"))
    )
    (net (code "161") (name "unconnected-(IC1-NC.2-Pad9)") (class "Default")
      (node (ref "IC1") (pin "9") (pinfunction "NC.2_9") (pintype "bidirectional"))
    )
    (net (code "162") (name "unconnected-(IC1-NC.3-Pad12)") (class "Default")
      (node (ref "IC1") (pin "12") (pinfunction "NC.3_12") (pintype "bidirectional"))
    )
    (net (code "163") (name "unconnected-(IC1-NC.4-Pad14)") (class "Default")
      (node (ref "IC1") (pin "14") (pinfunction "NC.4_14") (pintype "bidirectional"))
    )
    (net (code "164") (name "unconnected-(IC1-NC.5-Pad15)") (class "Default")
      (node (ref "IC1") (pin "15") (pinfunction "NC.5_15") (pintype "bidirectional"))
    )
    (net (code "165") (name "unconnected-(IC1-NC.6-Pad16)") (class "Default")
      (node (ref "IC1") (pin "16") (pinfunction "NC.6_16") (pintype "bidirectional"))
    )
    (net (code "166") (name "unconnected-(IC1-{slash}CEO-Pad13)") (class "Default")
      (node (ref "IC1") (pin "13") (pinfunction "/CEO_13") (pintype "bidirectional"))
    )
    (net (code "167") (name "unconnected-(REG1.2-VOUT2-Pad2)") (class "Default")
      (node (ref "REG1.2") (pin "2") (pinfunction "VOUT2_2") (pintype "bidirectional"))
    )
    (net (code "168") (name "unconnected-(REG2.5-VOUT2-Pad2)") (class "Default")
      (node (ref "REG2.5") (pin "2") (pinfunction "VOUT2_2") (pintype "bidirectional"))
    )
    (net (code "169") (name "unconnected-(REG3.3-VOUT2-Pad2)") (class "Default")
      (node (ref "REG3.3") (pin "2") (pinfunction "VOUT2_2") (pintype "bidirectional"))
    )
    (net (code "170") (name "unconnected-(U$2-TRI-PadENA)") (class "Default")
      (node (ref "U$2") (pin "ENA") (pinfunction "TRI_ENA") (pintype "input"))
    )
    (net (code "171") (name "unconnected-(U$3-CARD_DETECT-PadCD)") (class "Default")
      (node (ref "U$3") (pin "CD") (pinfunction "CARD_DETECT_CD") (pintype "passive"))
    )
    (net (code "172") (name "unconnected-(U$3-DAT1-Pad8)") (class "Default")
      (node (ref "U$3") (pin "8") (pinfunction "DAT1_8") (pintype "bidirectional"))
    )
    (net (code "173") (name "unconnected-(U$3-DAT2-Pad9)") (class "Default")
      (node (ref "U$3") (pin "9") (pinfunction "DAT2_9") (pintype "bidirectional"))
    )
    (net (code "174") (name "unconnected-(U$3-WRITE_PROTECT-PadWP)") (class "Default")
      (node (ref "U$3") (pin "WP") (pinfunction "WRITE_PROTECT_WP") (pintype "passive"))
    )
    (net (code "175") (name "unconnected-(U1N-HSWAP_EN-PadP142)") (class "Default")
      (node (ref "U1") (pin "P142") (pinfunction "HSWAP_EN_P142") (pintype "bidirectional"))
    )
    (net (code "176") (name "unconnected-(X1-Pad10)") (class "Default")
      (node (ref "X1") (pin "10") (pinfunction "10_10") (pintype "passive"))
    )
    (net (code "177") (name "unconnected-(X1-Pad12)") (class "Default")
      (node (ref "X1") (pin "12") (pinfunction "12_12") (pintype "passive"))
    )
    (net (code "178") (name "unconnected-(X3-Pad2)") (class "Default")
      (node (ref "X3") (pin "2") (pinfunction "2_2") (pintype "passive"))
    )
    (net (code "179") (name "unconnected-(X3-Pad8)") (class "Default")
      (node (ref "X3") (pin "8") (pinfunction "8_8") (pintype "passive"))
    )
    (net (code "180") (name "unconnected-(X4-PadG2)") (class "Default")
      (node (ref "X4") (pin "G2") (pinfunction "G2_G2") (pintype "passive"))
    )
    (net (code "181") (name "unconnected-(X5-PadG2)") (class "Default")
      (node (ref "X5") (pin "G2") (pinfunction "G2_G2") (pintype "passive"))
    )
    (net (code "182") (name "unconnected-(X6-Pad1)") (class "Default")
      (node (ref "X6") (pin "1") (pinfunction "1_1") (pintype "passive"))
    )
  )
)
